# 64CharTestDisp.net
KiCad netlist of a schematic drawn in EAGLE
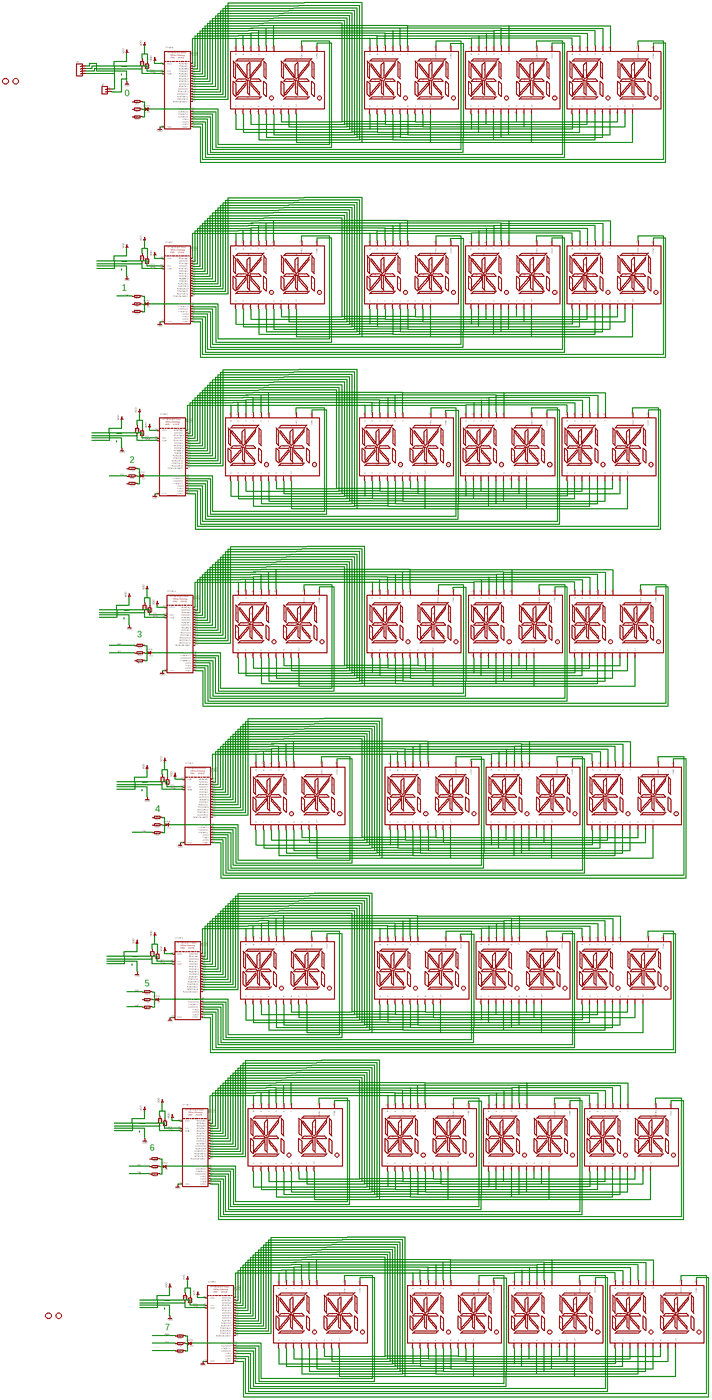
[diagram p0: schematic, sheet 1, overview]
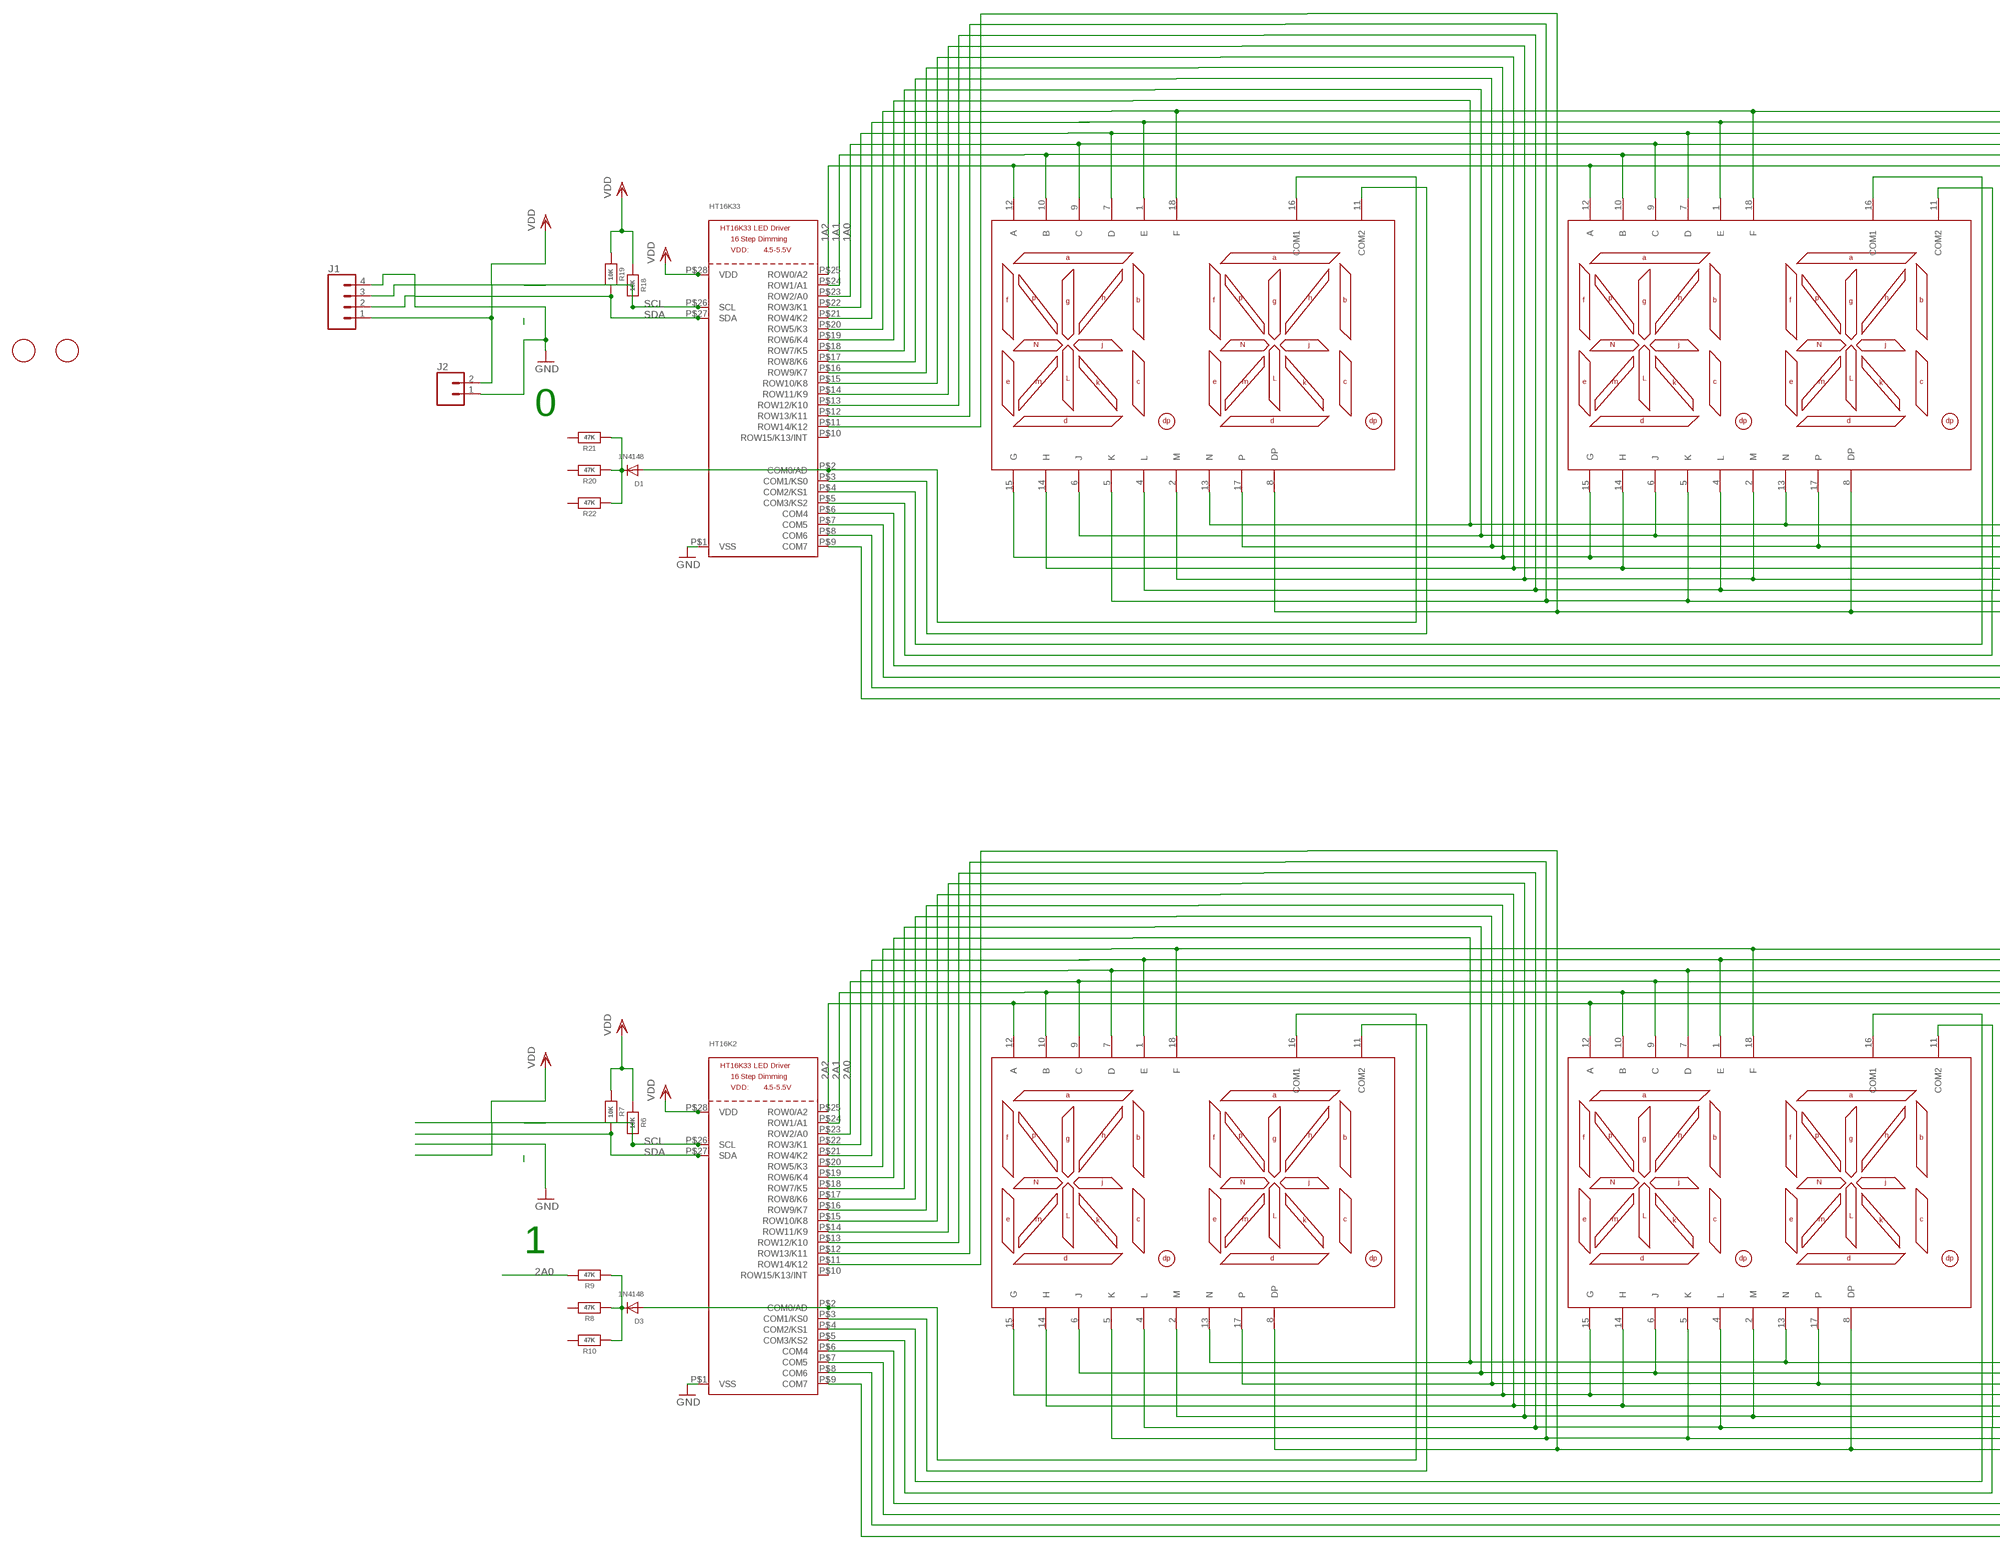
[diagram p1: schematic, sheet 1, part 1 of 8]
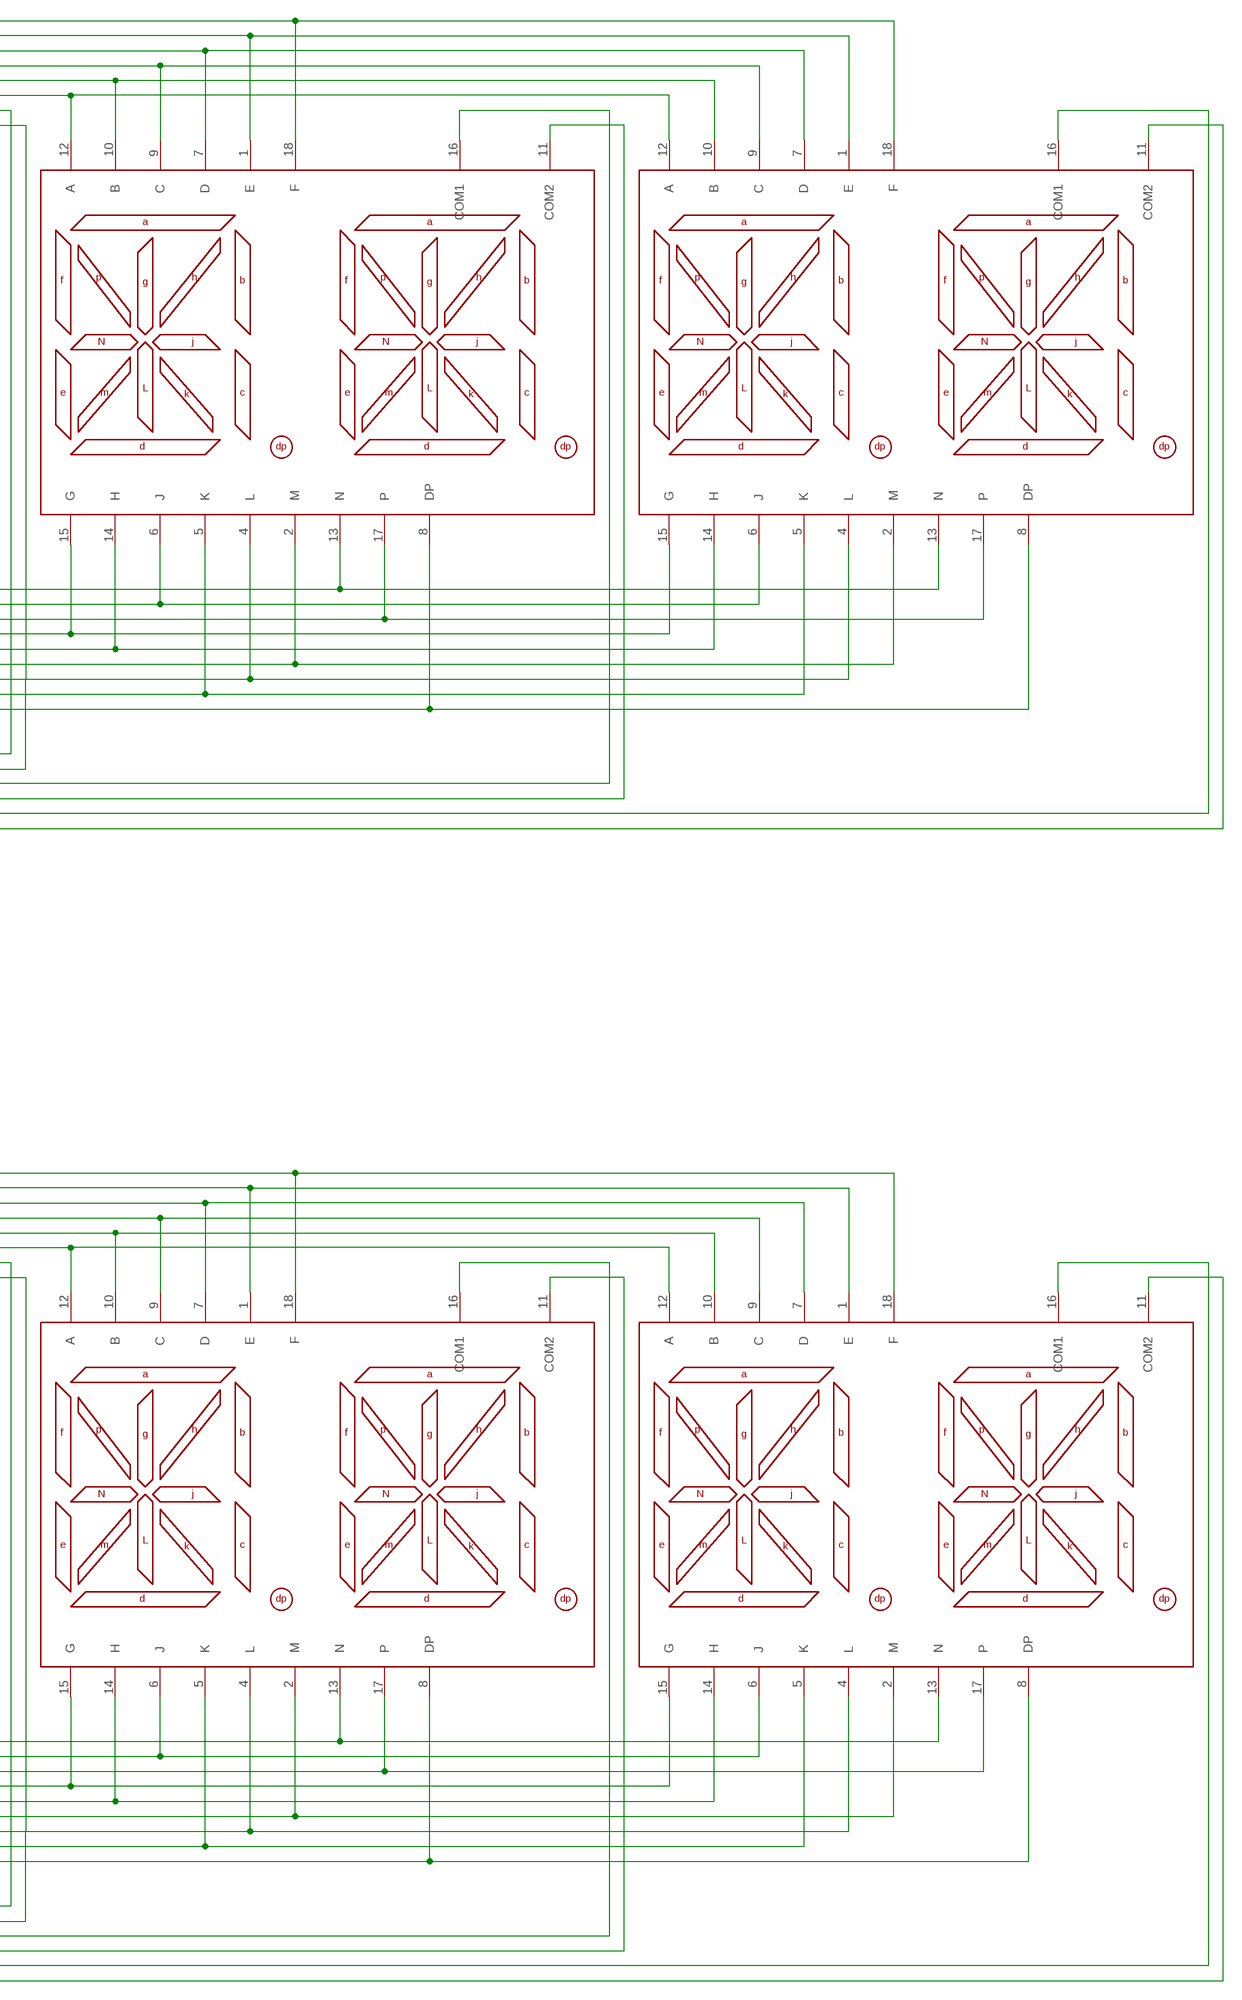
[diagram p2: schematic, sheet 1, part 2 of 8]
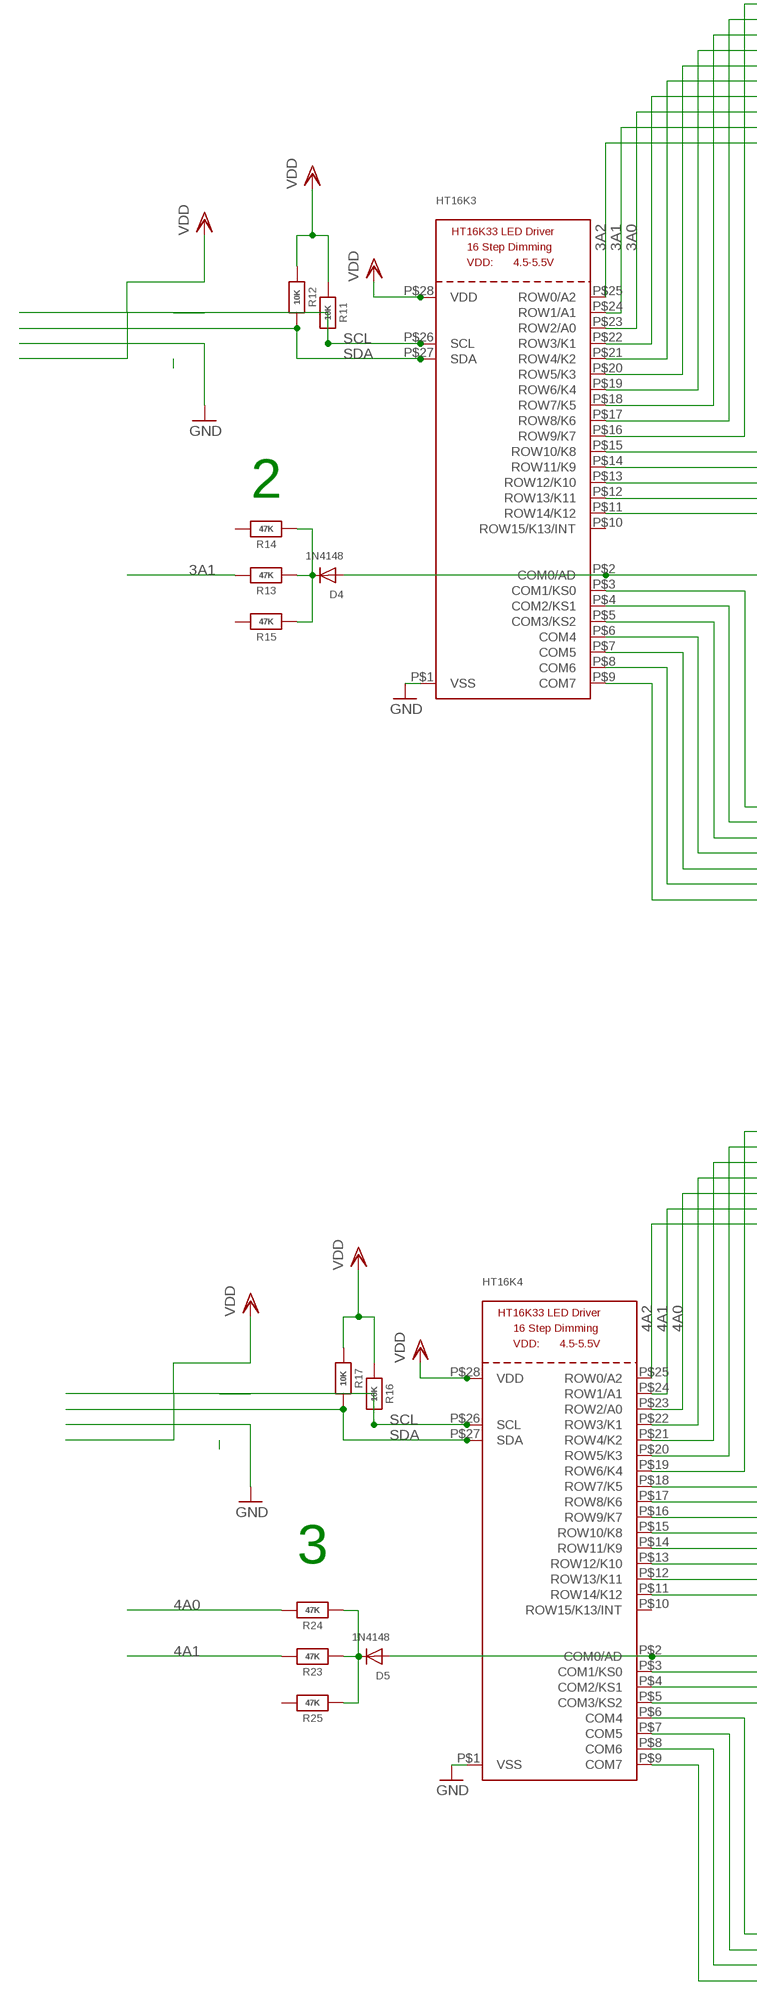
[diagram p3: schematic, sheet 1, part 3 of 8]
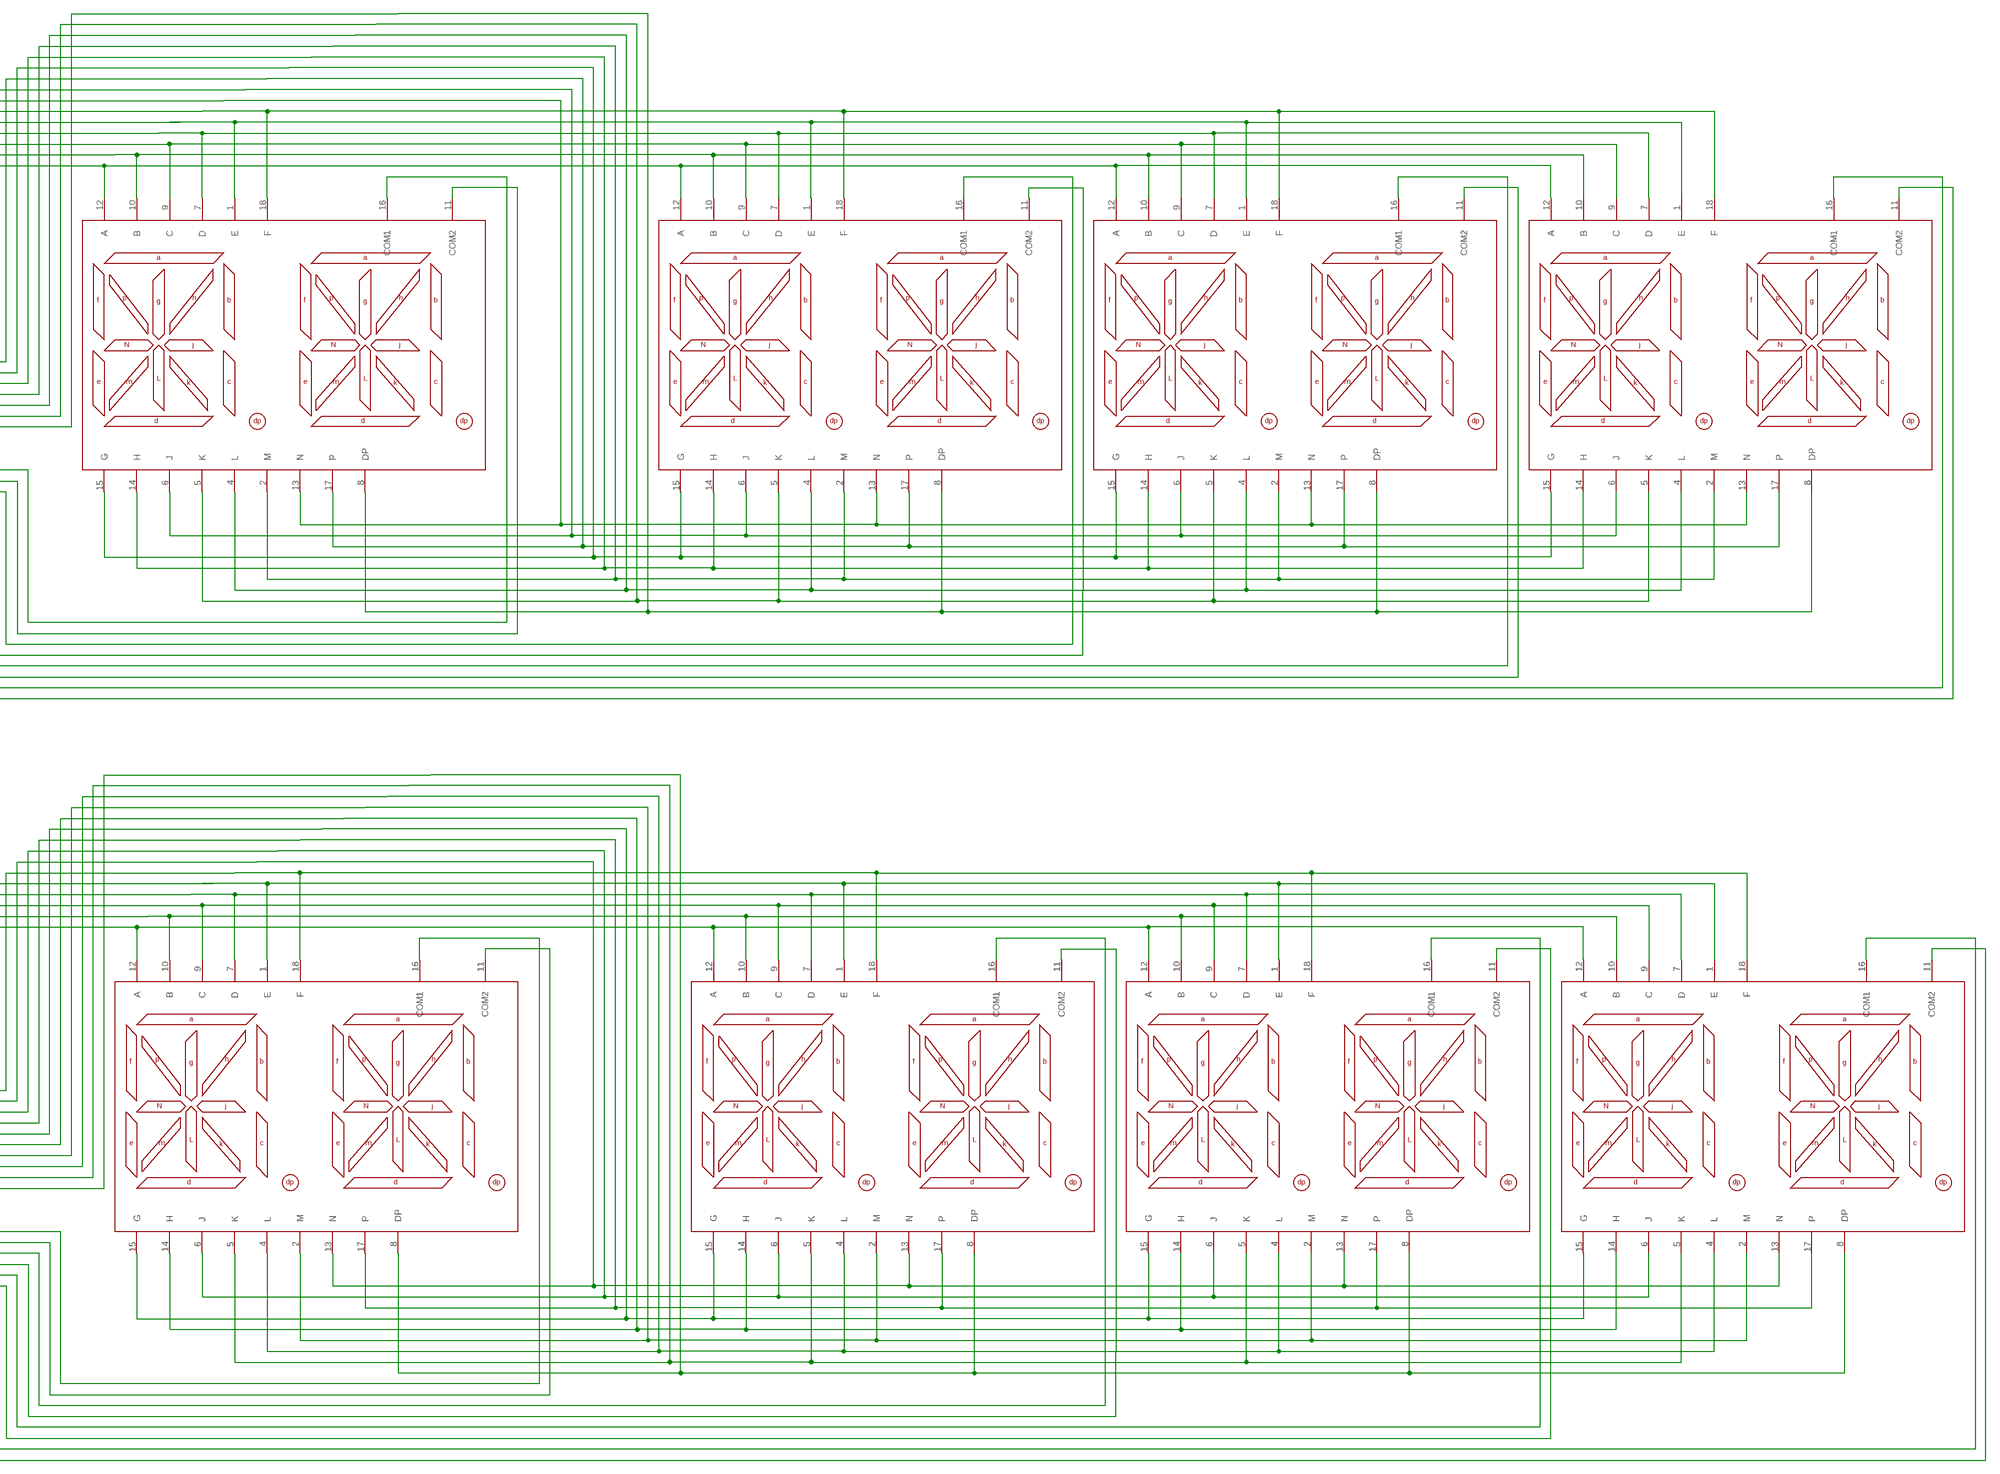
[diagram p4: schematic, sheet 1, part 4 of 8]
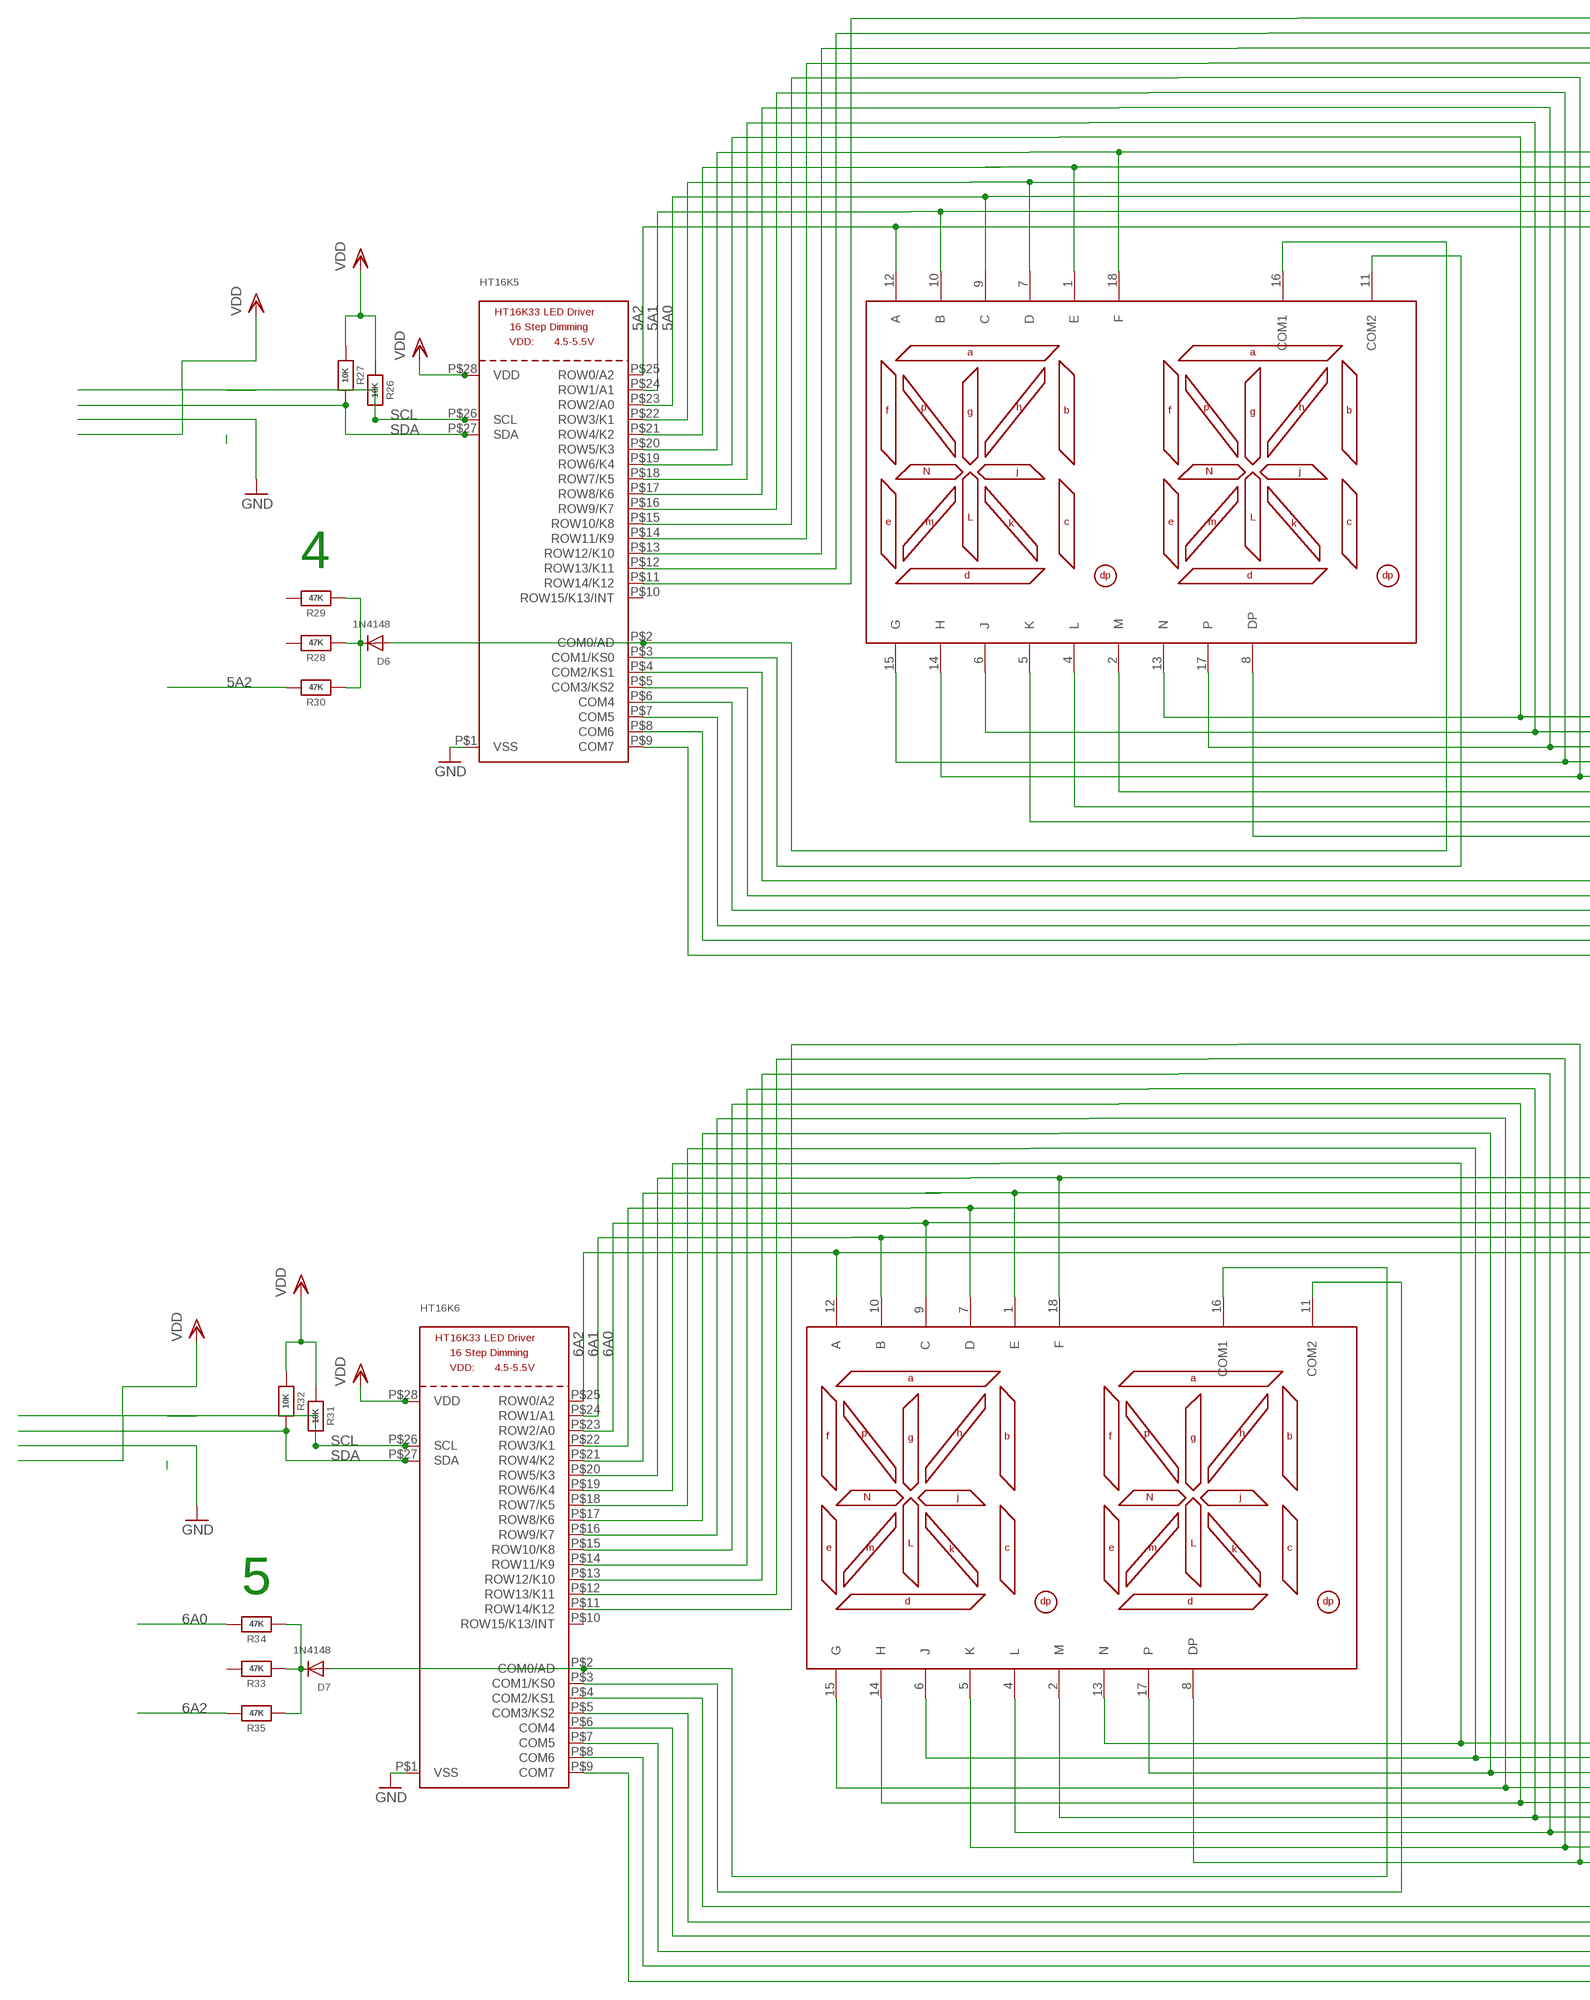
[diagram p5: schematic, sheet 1, part 5 of 8]
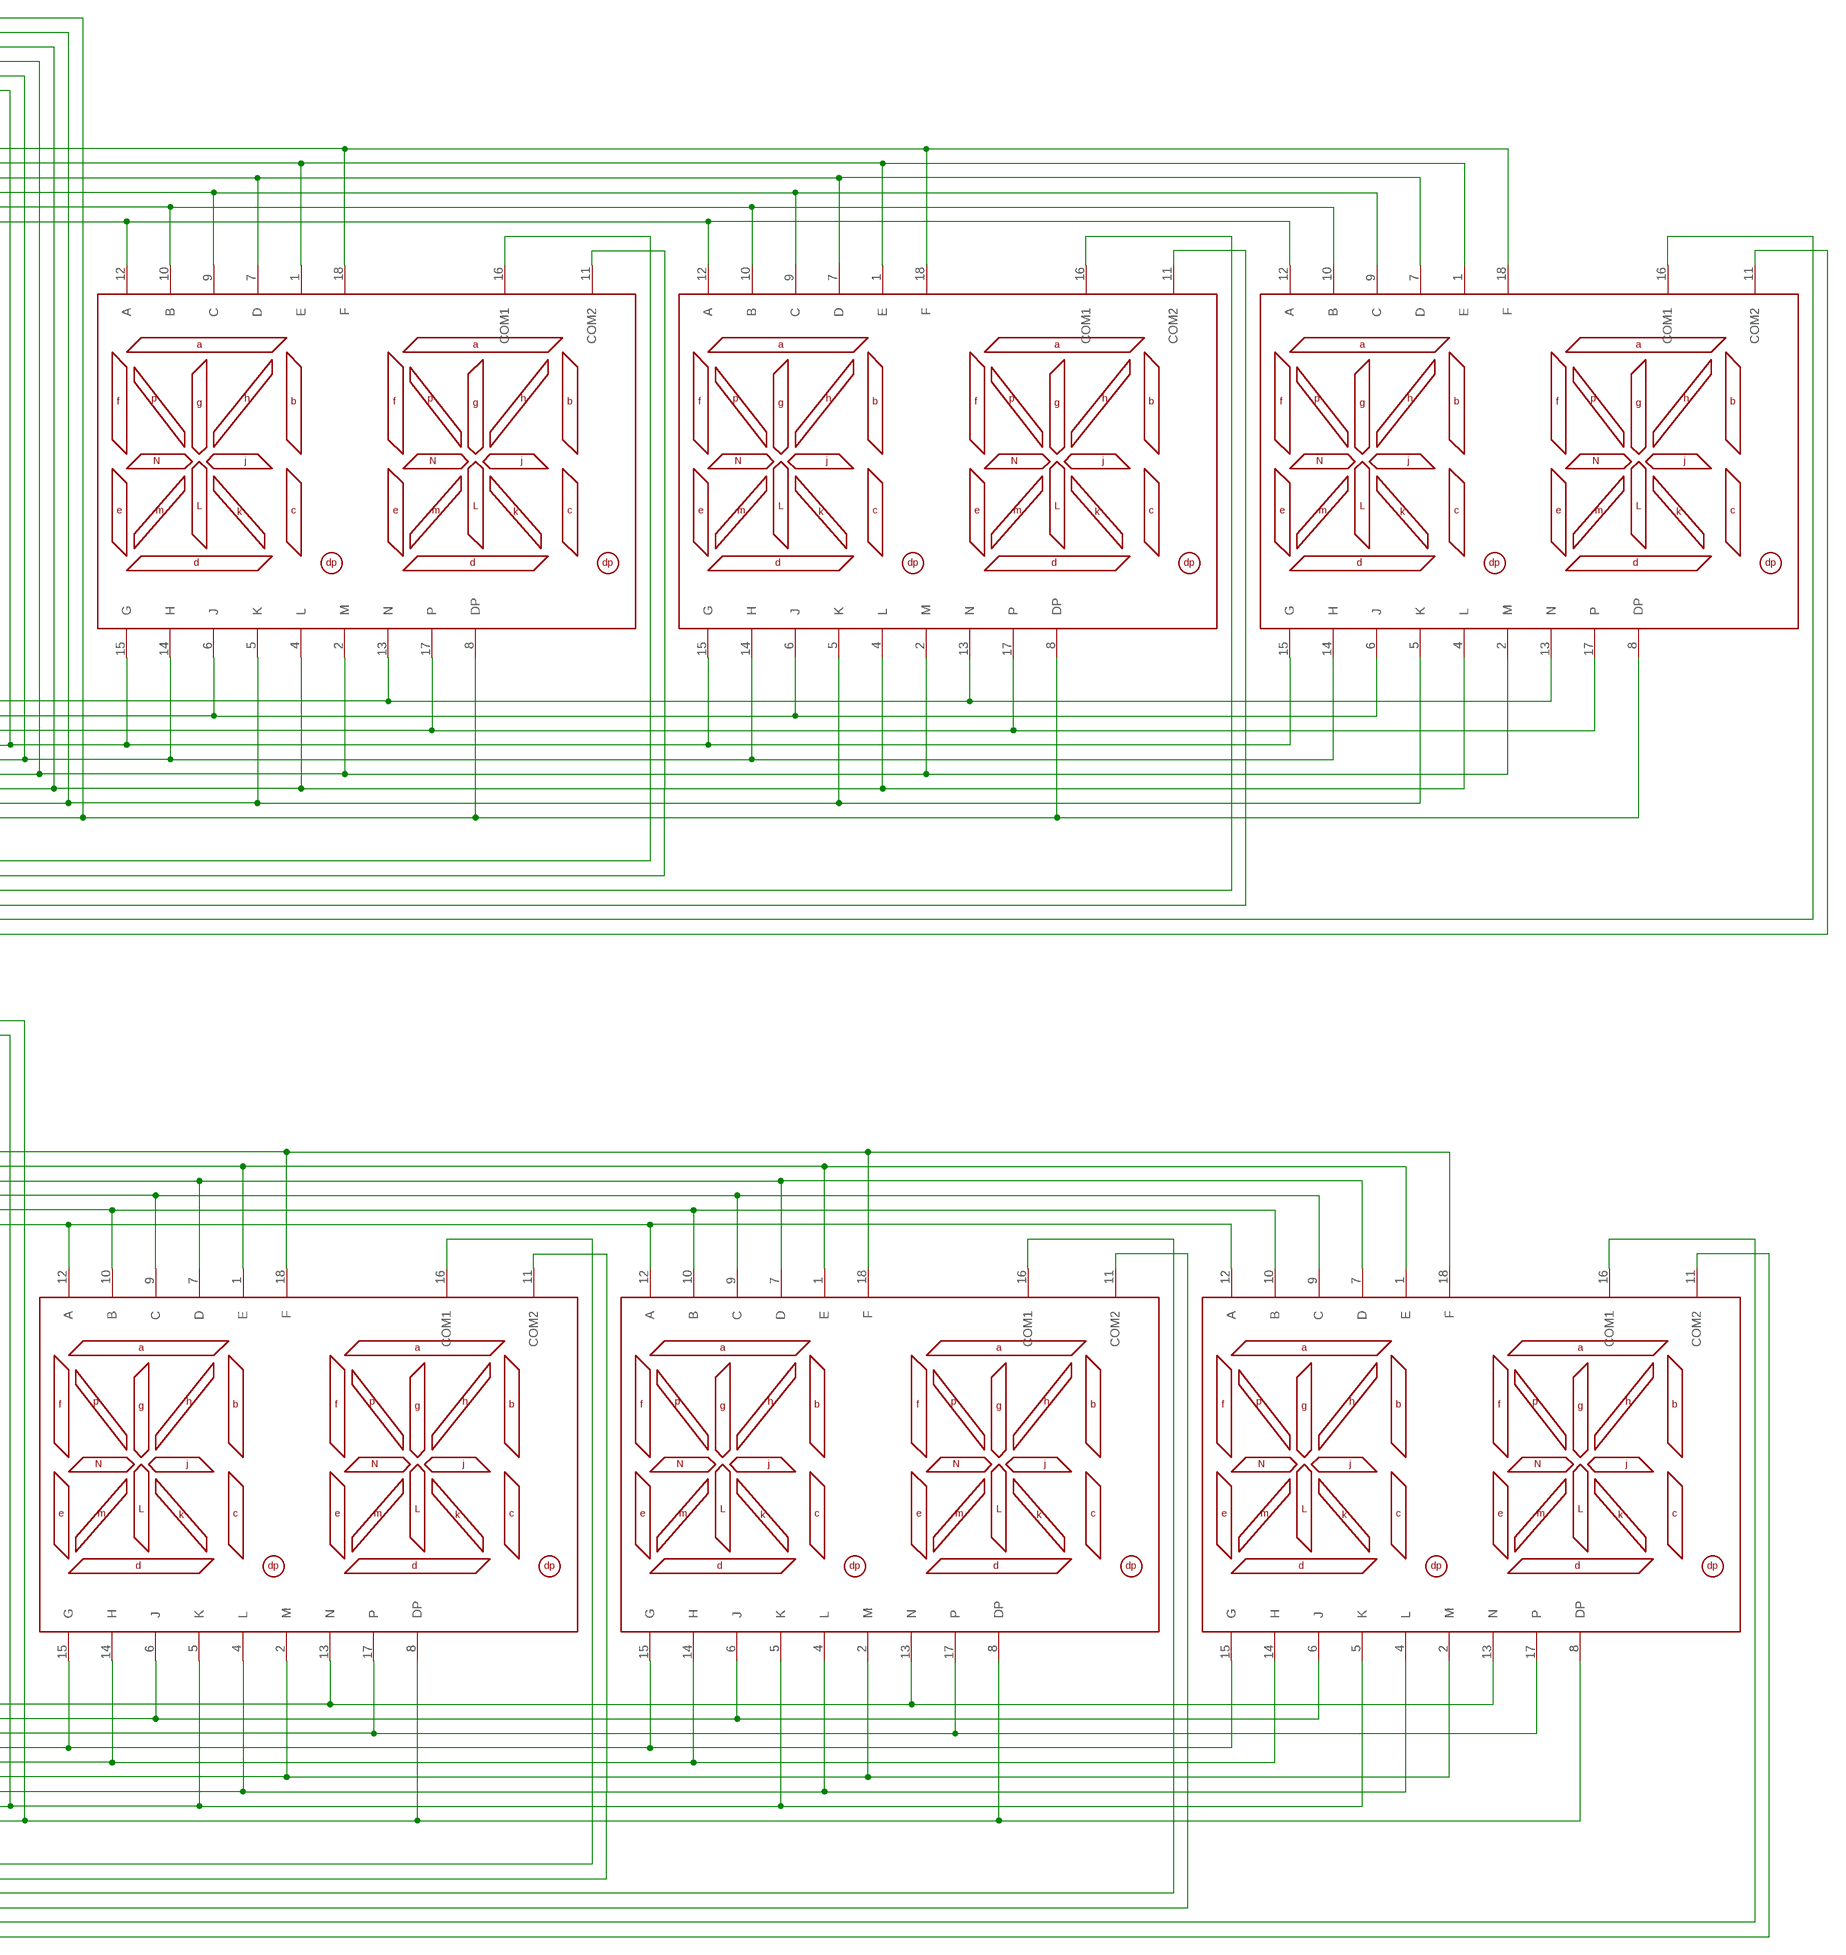
[diagram p6: schematic, sheet 1, part 6 of 8]
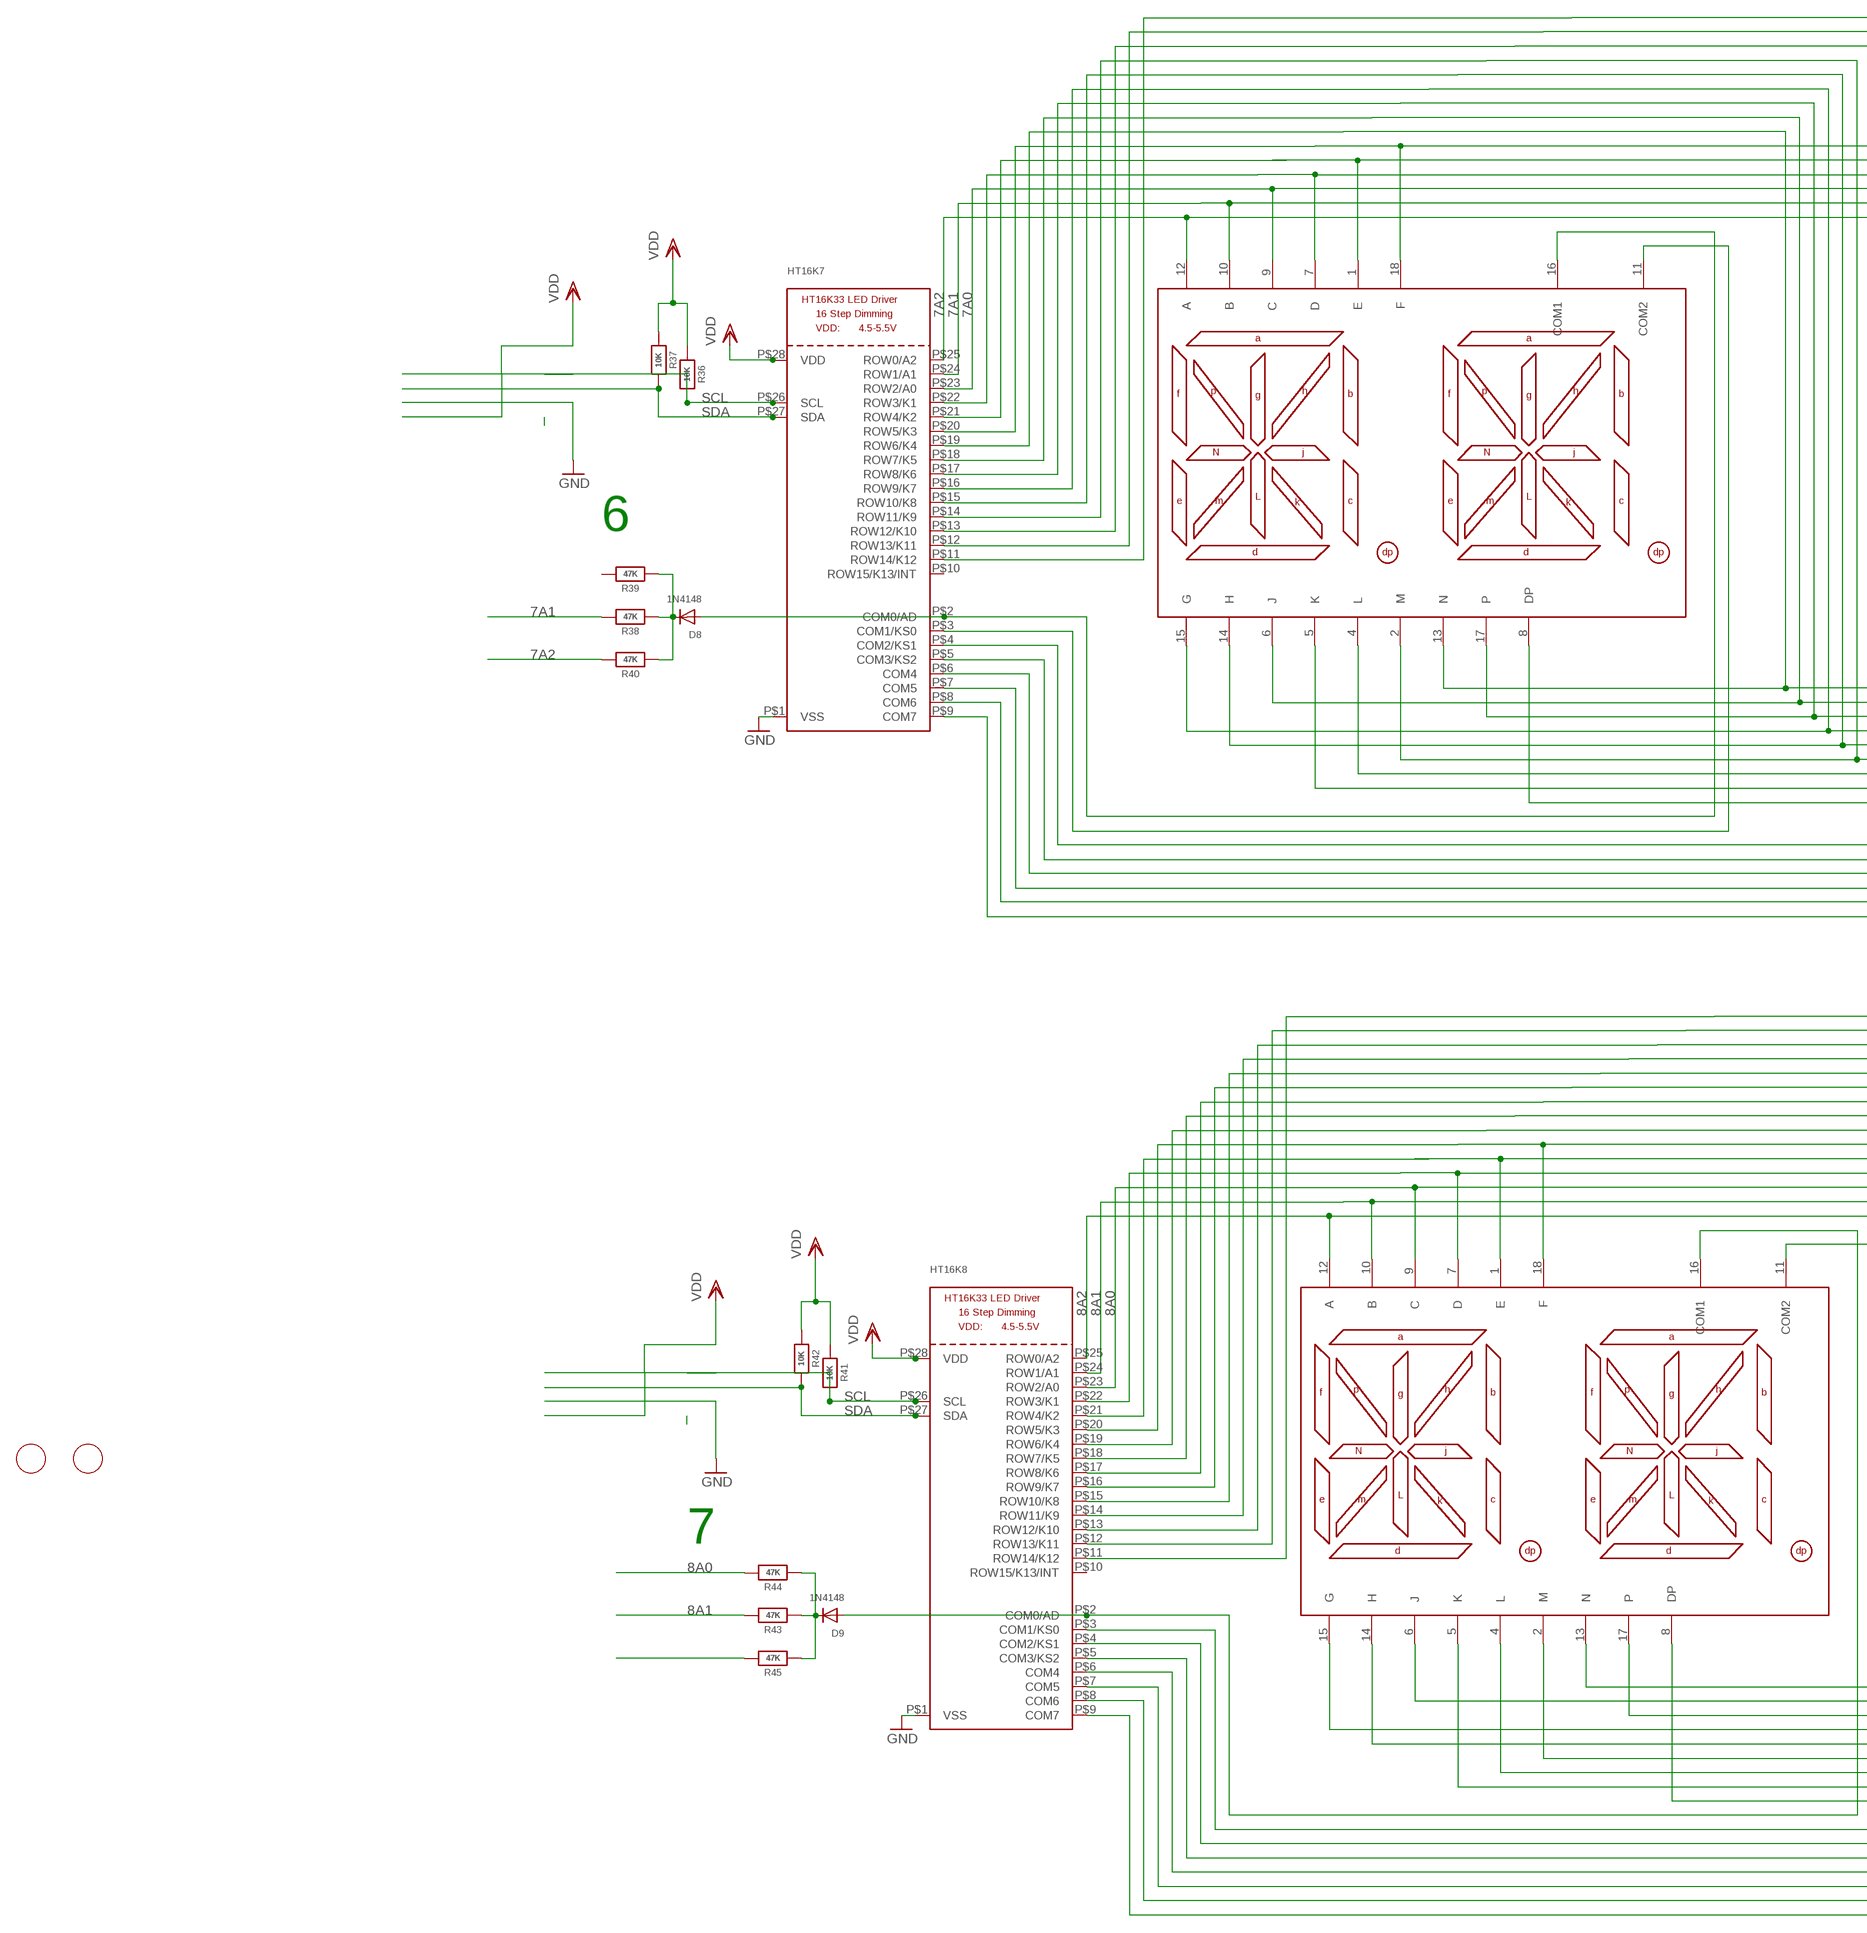
[diagram p7: schematic, sheet 1, part 7 of 8]
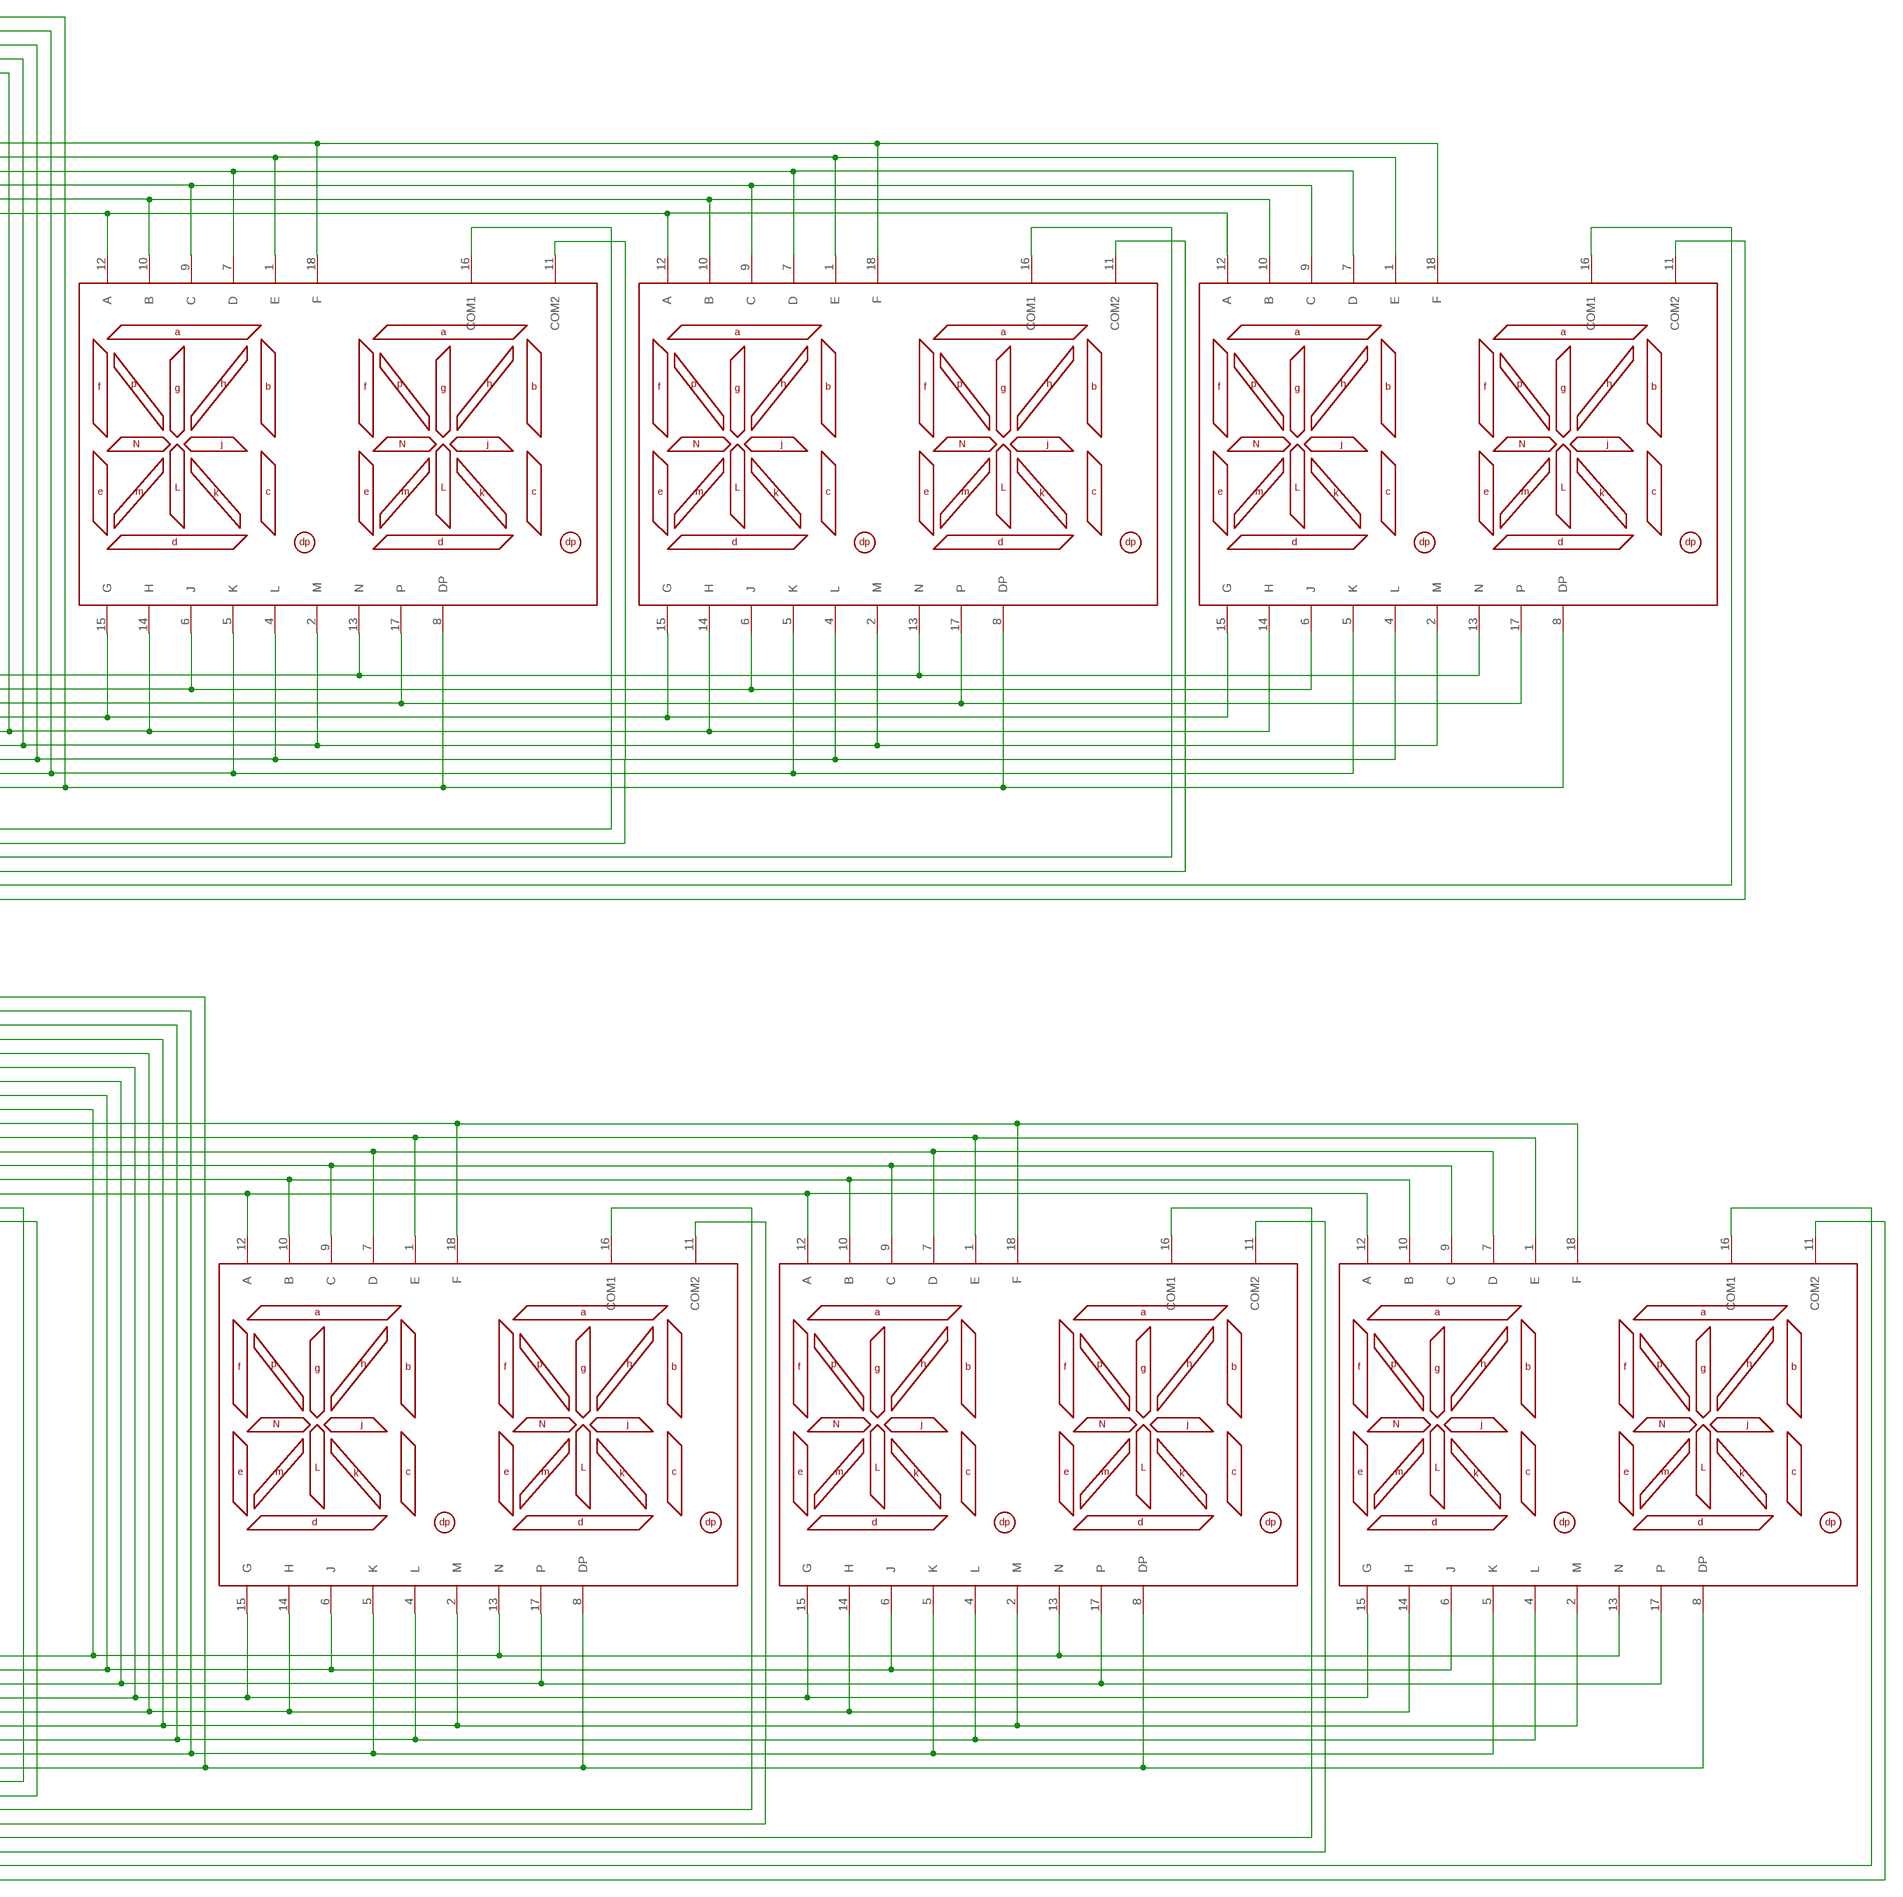
[diagram p8: schematic, sheet 1, part 8 of 8]

(export (version "E")
  (design (tool "Eeschema 10.0.6"))
  (components
    (comp (ref "D1")
      (value "1N4148")
      (footprint "eagle-import:SOD-323F")
      (libsource (lib "eagle-import") (part "DIODESOD-323F"))
    )
    (comp (ref "D3")
      (value "1N4148")
      (footprint "eagle-import:SOD-323F")
      (libsource (lib "eagle-import") (part "DIODESOD-323F"))
    )
    (comp (ref "D4")
      (value "1N4148")
      (footprint "eagle-import:SOD-323F")
      (libsource (lib "eagle-import") (part "DIODESOD-323F"))
    )
    (comp (ref "D5")
      (value "1N4148")
      (footprint "eagle-import:SOD-323F")
      (libsource (lib "eagle-import") (part "DIODESOD-323F"))
    )
    (comp (ref "D6")
      (value "1N4148")
      (footprint "eagle-import:SOD-323F")
      (libsource (lib "eagle-import") (part "DIODESOD-323F"))
    )
    (comp (ref "D7")
      (value "1N4148")
      (footprint "eagle-import:SOD-323F")
      (libsource (lib "eagle-import") (part "DIODESOD-323F"))
    )
    (comp (ref "D8")
      (value "1N4148")
      (footprint "eagle-import:SOD-323F")
      (libsource (lib "eagle-import") (part "DIODESOD-323F"))
    )
    (comp (ref "D9")
      (value "1N4148")
      (footprint "eagle-import:SOD-323F")
      (libsource (lib "eagle-import") (part "DIODESOD-323F"))
    )
    (comp (ref "HT16K2")
      (value "HT16K33_SOP28_SKINNY")
      (footprint "eagle-import:SOP28_300MIL_SKINNY")
      (libsource (lib "eagle-import") (part "HT16K33_SOP28_SKINNY"))
    )
    (comp (ref "HT16K3")
      (value "HT16K33_SOP28_SKINNY")
      (footprint "eagle-import:SOP28_300MIL_SKINNY")
      (libsource (lib "eagle-import") (part "HT16K33_SOP28_SKINNY"))
    )
    (comp (ref "HT16K4")
      (value "HT16K33_SOP28_SKINNY")
      (footprint "eagle-import:SOP28_300MIL_SKINNY")
      (libsource (lib "eagle-import") (part "HT16K33_SOP28_SKINNY"))
    )
    (comp (ref "HT16K5")
      (value "HT16K33_SOP28_SKINNY")
      (footprint "eagle-import:SOP28_300MIL_SKINNY")
      (libsource (lib "eagle-import") (part "HT16K33_SOP28_SKINNY"))
    )
    (comp (ref "HT16K6")
      (value "HT16K33_SOP28_SKINNY")
      (footprint "eagle-import:SOP28_300MIL_SKINNY")
      (libsource (lib "eagle-import") (part "HT16K33_SOP28_SKINNY"))
    )
    (comp (ref "HT16K7")
      (value "HT16K33_SOP28_SKINNY")
      (footprint "eagle-import:SOP28_300MIL_SKINNY")
      (libsource (lib "eagle-import") (part "HT16K33_SOP28_SKINNY"))
    )
    (comp (ref "HT16K8")
      (value "HT16K33_SOP28_SKINNY")
      (footprint "eagle-import:SOP28_300MIL_SKINNY")
      (libsource (lib "eagle-import") (part "HT16K33_SOP28_SKINNY"))
    )
    (comp (ref "HT16K33")
      (value "HT16K33_SOP28_SKINNY")
      (footprint "eagle-import:SOP28_300MIL_SKINNY")
      (libsource (lib "eagle-import") (part "HT16K33_SOP28_SKINNY"))
    )
    (comp (ref "J1")
      (value "CONN_04JST-PTH-VERT")
      (footprint "eagle-import:JST-4-PTH-VERT")
      (libsource (lib "eagle-import") (part "CONN_04JST-PTH-VERT"))
    )
    (comp (ref "J2")
      (value "CONN_023.5MM")
      (footprint "eagle-import:SCREWTERMINAL-3.5MM-2")
      (libsource (lib "eagle-import") (part "CONN_023.5MM"))
    )
    (comp (ref "R6")
      (value "10K")
      (footprint "eagle-import:0805-NO")
      (libsource (lib "eagle-import") (part "RESISTOR0805_NOOUTLINE"))
    )
    (comp (ref "R7")
      (value "10K")
      (footprint "eagle-import:0805-NO")
      (libsource (lib "eagle-import") (part "RESISTOR0805_NOOUTLINE"))
    )
    (comp (ref "R8")
      (value "47K")
      (footprint "eagle-import:0805-NO")
      (libsource (lib "eagle-import") (part "RESISTOR0805_NOOUTLINE"))
    )
    (comp (ref "R9")
      (value "47K")
      (footprint "eagle-import:0805-NO")
      (libsource (lib "eagle-import") (part "RESISTOR0805_NOOUTLINE"))
    )
    (comp (ref "R10")
      (value "47K")
      (footprint "eagle-import:0805-NO")
      (libsource (lib "eagle-import") (part "RESISTOR0805_NOOUTLINE"))
    )
    (comp (ref "R11")
      (value "10K")
      (footprint "eagle-import:0805-NO")
      (libsource (lib "eagle-import") (part "RESISTOR0805_NOOUTLINE"))
    )
    (comp (ref "R12")
      (value "10K")
      (footprint "eagle-import:0805-NO")
      (libsource (lib "eagle-import") (part "RESISTOR0805_NOOUTLINE"))
    )
    (comp (ref "R13")
      (value "47K")
      (footprint "eagle-import:0805-NO")
      (libsource (lib "eagle-import") (part "RESISTOR0805_NOOUTLINE"))
    )
    (comp (ref "R14")
      (value "47K")
      (footprint "eagle-import:0805-NO")
      (libsource (lib "eagle-import") (part "RESISTOR0805_NOOUTLINE"))
    )
    (comp (ref "R15")
      (value "47K")
      (footprint "eagle-import:0805-NO")
      (libsource (lib "eagle-import") (part "RESISTOR0805_NOOUTLINE"))
    )
    (comp (ref "R16")
      (value "10K")
      (footprint "eagle-import:0805-NO")
      (libsource (lib "eagle-import") (part "RESISTOR0805_NOOUTLINE"))
    )
    (comp (ref "R17")
      (value "10K")
      (footprint "eagle-import:0805-NO")
      (libsource (lib "eagle-import") (part "RESISTOR0805_NOOUTLINE"))
    )
    (comp (ref "R18")
      (value "10K")
      (footprint "eagle-import:0805-NO")
      (libsource (lib "eagle-import") (part "RESISTOR0805_NOOUTLINE"))
    )
    (comp (ref "R19")
      (value "10K")
      (footprint "eagle-import:0805-NO")
      (libsource (lib "eagle-import") (part "RESISTOR0805_NOOUTLINE"))
    )
    (comp (ref "R20")
      (value "47K")
      (footprint "eagle-import:0805-NO")
      (libsource (lib "eagle-import") (part "RESISTOR0805_NOOUTLINE"))
    )
    (comp (ref "R21")
      (value "47K")
      (footprint "eagle-import:0805-NO")
      (libsource (lib "eagle-import") (part "RESISTOR0805_NOOUTLINE"))
    )
    (comp (ref "R22")
      (value "47K")
      (footprint "eagle-import:0805-NO")
      (libsource (lib "eagle-import") (part "RESISTOR0805_NOOUTLINE"))
    )
    (comp (ref "R23")
      (value "47K")
      (footprint "eagle-import:0805-NO")
      (libsource (lib "eagle-import") (part "RESISTOR0805_NOOUTLINE"))
    )
    (comp (ref "R24")
      (value "47K")
      (footprint "eagle-import:0805-NO")
      (libsource (lib "eagle-import") (part "RESISTOR0805_NOOUTLINE"))
    )
    (comp (ref "R25")
      (value "47K")
      (footprint "eagle-import:0805-NO")
      (libsource (lib "eagle-import") (part "RESISTOR0805_NOOUTLINE"))
    )
    (comp (ref "R26")
      (value "10K")
      (footprint "eagle-import:0805-NO")
      (libsource (lib "eagle-import") (part "RESISTOR0805_NOOUTLINE"))
    )
    (comp (ref "R27")
      (value "10K")
      (footprint "eagle-import:0805-NO")
      (libsource (lib "eagle-import") (part "RESISTOR0805_NOOUTLINE"))
    )
    (comp (ref "R28")
      (value "47K")
      (footprint "eagle-import:0805-NO")
      (libsource (lib "eagle-import") (part "RESISTOR0805_NOOUTLINE"))
    )
    (comp (ref "R29")
      (value "47K")
      (footprint "eagle-import:0805-NO")
      (libsource (lib "eagle-import") (part "RESISTOR0805_NOOUTLINE"))
    )
    (comp (ref "R30")
      (value "47K")
      (footprint "eagle-import:0805-NO")
      (libsource (lib "eagle-import") (part "RESISTOR0805_NOOUTLINE"))
    )
    (comp (ref "R31")
      (value "10K")
      (footprint "eagle-import:0805-NO")
      (libsource (lib "eagle-import") (part "RESISTOR0805_NOOUTLINE"))
    )
    (comp (ref "R32")
      (value "10K")
      (footprint "eagle-import:0805-NO")
      (libsource (lib "eagle-import") (part "RESISTOR0805_NOOUTLINE"))
    )
    (comp (ref "R33")
      (value "47K")
      (footprint "eagle-import:0805-NO")
      (libsource (lib "eagle-import") (part "RESISTOR0805_NOOUTLINE"))
    )
    (comp (ref "R34")
      (value "47K")
      (footprint "eagle-import:0805-NO")
      (libsource (lib "eagle-import") (part "RESISTOR0805_NOOUTLINE"))
    )
    (comp (ref "R35")
      (value "47K")
      (footprint "eagle-import:0805-NO")
      (libsource (lib "eagle-import") (part "RESISTOR0805_NOOUTLINE"))
    )
    (comp (ref "R36")
      (value "10K")
      (footprint "eagle-import:0805-NO")
      (libsource (lib "eagle-import") (part "RESISTOR0805_NOOUTLINE"))
    )
    (comp (ref "R37")
      (value "10K")
      (footprint "eagle-import:0805-NO")
      (libsource (lib "eagle-import") (part "RESISTOR0805_NOOUTLINE"))
    )
    (comp (ref "R38")
      (value "47K")
      (footprint "eagle-import:0805-NO")
      (libsource (lib "eagle-import") (part "RESISTOR0805_NOOUTLINE"))
    )
    (comp (ref "R39")
      (value "47K")
      (footprint "eagle-import:0805-NO")
      (libsource (lib "eagle-import") (part "RESISTOR0805_NOOUTLINE"))
    )
    (comp (ref "R40")
      (value "47K")
      (footprint "eagle-import:0805-NO")
      (libsource (lib "eagle-import") (part "RESISTOR0805_NOOUTLINE"))
    )
    (comp (ref "R41")
      (value "10K")
      (footprint "eagle-import:0805-NO")
      (libsource (lib "eagle-import") (part "RESISTOR0805_NOOUTLINE"))
    )
    (comp (ref "R42")
      (value "10K")
      (footprint "eagle-import:0805-NO")
      (libsource (lib "eagle-import") (part "RESISTOR0805_NOOUTLINE"))
    )
    (comp (ref "R43")
      (value "47K")
      (footprint "eagle-import:0805-NO")
      (libsource (lib "eagle-import") (part "RESISTOR0805_NOOUTLINE"))
    )
    (comp (ref "R44")
      (value "47K")
      (footprint "eagle-import:0805-NO")
      (libsource (lib "eagle-import") (part "RESISTOR0805_NOOUTLINE"))
    )
    (comp (ref "R45")
      (value "47K")
      (footprint "eagle-import:0805-NO")
      (libsource (lib "eagle-import") (part "RESISTOR0805_NOOUTLINE"))
    )
    (comp (ref "U$2")
      (value "BIG14SEG")
      (footprint "eagle-import:HDSP")
      (libsource (lib "eagle-import") (part "BIG14SEG"))
    )
    (comp (ref "U$3")
      (value "BIG14SEG")
      (footprint "eagle-import:HDSP")
      (libsource (lib "eagle-import") (part "BIG14SEG"))
    )
    (comp (ref "U$4")
      (value "BIG14SEG")
      (footprint "eagle-import:HDSP")
      (libsource (lib "eagle-import") (part "BIG14SEG"))
    )
    (comp (ref "U$5")
      (value "BIG14SEG")
      (footprint "eagle-import:HDSP")
      (libsource (lib "eagle-import") (part "BIG14SEG"))
    )
    (comp (ref "U$11")
      (value "BIG14SEG")
      (footprint "eagle-import:HDSP")
      (libsource (lib "eagle-import") (part "BIG14SEG"))
    )
    (comp (ref "U$12")
      (value "BIG14SEG")
      (footprint "eagle-import:HDSP")
      (libsource (lib "eagle-import") (part "BIG14SEG"))
    )
    (comp (ref "U$13")
      (value "BIG14SEG")
      (footprint "eagle-import:HDSP")
      (libsource (lib "eagle-import") (part "BIG14SEG"))
    )
    (comp (ref "U$14")
      (value "BIG14SEG")
      (footprint "eagle-import:HDSP")
      (libsource (lib "eagle-import") (part "BIG14SEG"))
    )
    (comp (ref "U$15")
      (value "BIG14SEG")
      (footprint "eagle-import:HDSP")
      (libsource (lib "eagle-import") (part "BIG14SEG"))
    )
    (comp (ref "U$16")
      (value "BIG14SEG")
      (footprint "eagle-import:HDSP")
      (libsource (lib "eagle-import") (part "BIG14SEG"))
    )
    (comp (ref "U$17")
      (value "BIG14SEG")
      (footprint "eagle-import:HDSP")
      (libsource (lib "eagle-import") (part "BIG14SEG"))
    )
    (comp (ref "U$18")
      (value "BIG14SEG")
      (footprint "eagle-import:HDSP")
      (libsource (lib "eagle-import") (part "BIG14SEG"))
    )
    (comp (ref "U$19")
      (value "BIG14SEG")
      (footprint "eagle-import:HDSP")
      (libsource (lib "eagle-import") (part "BIG14SEG"))
    )
    (comp (ref "U$20")
      (value "BIG14SEG")
      (footprint "eagle-import:HDSP")
      (libsource (lib "eagle-import") (part "BIG14SEG"))
    )
    (comp (ref "U$21")
      (value "BIG14SEG")
      (footprint "eagle-import:HDSP")
      (libsource (lib "eagle-import") (part "BIG14SEG"))
    )
    (comp (ref "U$22")
      (value "BIG14SEG")
      (footprint "eagle-import:HDSP")
      (libsource (lib "eagle-import") (part "BIG14SEG"))
    )
    (comp (ref "U$23")
      (value "BIG14SEG")
      (footprint "eagle-import:HDSP")
      (libsource (lib "eagle-import") (part "BIG14SEG"))
    )
    (comp (ref "U$24")
      (value "BIG14SEG")
      (footprint "eagle-import:HDSP")
      (libsource (lib "eagle-import") (part "BIG14SEG"))
    )
    (comp (ref "U$25")
      (value "BIG14SEG")
      (footprint "eagle-import:HDSP")
      (libsource (lib "eagle-import") (part "BIG14SEG"))
    )
    (comp (ref "U$26")
      (value "BIG14SEG")
      (footprint "eagle-import:HDSP")
      (libsource (lib "eagle-import") (part "BIG14SEG"))
    )
    (comp (ref "U$27")
      (value "BIG14SEG")
      (footprint "eagle-import:HDSP")
      (libsource (lib "eagle-import") (part "BIG14SEG"))
    )
    (comp (ref "U$28")
      (value "BIG14SEG")
      (footprint "eagle-import:HDSP")
      (libsource (lib "eagle-import") (part "BIG14SEG"))
    )
    (comp (ref "U$29")
      (value "BIG14SEG")
      (footprint "eagle-import:HDSP")
      (libsource (lib "eagle-import") (part "BIG14SEG"))
    )
    (comp (ref "U$30")
      (value "BIG14SEG")
      (footprint "eagle-import:HDSP")
      (libsource (lib "eagle-import") (part "BIG14SEG"))
    )
    (comp (ref "U$31")
      (value "BIG14SEG")
      (footprint "eagle-import:HDSP")
      (libsource (lib "eagle-import") (part "BIG14SEG"))
    )
    (comp (ref "U$32")
      (value "BIG14SEG")
      (footprint "eagle-import:HDSP")
      (libsource (lib "eagle-import") (part "BIG14SEG"))
    )
    (comp (ref "U$33")
      (value "BIG14SEG")
      (footprint "eagle-import:HDSP")
      (libsource (lib "eagle-import") (part "BIG14SEG"))
    )
    (comp (ref "U$34")
      (value "BIG14SEG")
      (footprint "eagle-import:HDSP")
      (libsource (lib "eagle-import") (part "BIG14SEG"))
    )
    (comp (ref "U$35")
      (value "KEYSTONESTANDOFF")
      (footprint "eagle-import:KEYSTONESTANDOFF")
      (libsource (lib "eagle-import") (part "KEYSTONESTANDOFF"))
    )
    (comp (ref "U$36")
      (value "KEYSTONESTANDOFF")
      (footprint "eagle-import:KEYSTONESTANDOFF")
      (libsource (lib "eagle-import") (part "KEYSTONESTANDOFF"))
    )
    (comp (ref "U$37")
      (value "BIG14SEG")
      (footprint "eagle-import:HDSP")
      (libsource (lib "eagle-import") (part "BIG14SEG"))
    )
    (comp (ref "U$38")
      (value "BIG14SEG")
      (footprint "eagle-import:HDSP")
      (libsource (lib "eagle-import") (part "BIG14SEG"))
    )
    (comp (ref "U$39")
      (value "BIG14SEG")
      (footprint "eagle-import:HDSP")
      (libsource (lib "eagle-import") (part "BIG14SEG"))
    )
    (comp (ref "U$40")
      (value "BIG14SEG")
      (footprint "eagle-import:HDSP")
      (libsource (lib "eagle-import") (part "BIG14SEG"))
    )
    (comp (ref "U$41")
      (value "KEYSTONESTANDOFF")
      (footprint "eagle-import:KEYSTONESTANDOFF")
      (libsource (lib "eagle-import") (part "KEYSTONESTANDOFF"))
    )
    (comp (ref "U$42")
      (value "KEYSTONESTANDOFF")
      (footprint "eagle-import:KEYSTONESTANDOFF")
      (libsource (lib "eagle-import") (part "KEYSTONESTANDOFF"))
    )
  )
  (nets
    (net (code "1") (name "/1A0") (class "Default")
      (node (ref "HT16K33") (pin "P$23") (pinfunction "ROW2/A0_P$23") (pintype "bidirectional"))
      (node (ref "U$2") (pin "9") (pinfunction "C_9") (pintype "bidirectional"))
      (node (ref "U$3") (pin "9") (pinfunction "C_9") (pintype "bidirectional"))
      (node (ref "U$4") (pin "9") (pinfunction "C_9") (pintype "bidirectional"))
      (node (ref "U$5") (pin "9") (pinfunction "C_9") (pintype "bidirectional"))
    )
    (net (code "2") (name "/1A1") (class "Default")
      (node (ref "HT16K33") (pin "P$24") (pinfunction "ROW1/A1_P$24") (pintype "bidirectional"))
      (node (ref "U$2") (pin "10") (pinfunction "B_10") (pintype "bidirectional"))
      (node (ref "U$3") (pin "10") (pinfunction "B_10") (pintype "bidirectional"))
      (node (ref "U$4") (pin "10") (pinfunction "B_10") (pintype "bidirectional"))
      (node (ref "U$5") (pin "10") (pinfunction "B_10") (pintype "bidirectional"))
    )
    (net (code "3") (name "/1A2") (class "Default")
      (node (ref "HT16K33") (pin "P$25") (pinfunction "ROW0/A2_P$25") (pintype "bidirectional"))
      (node (ref "U$2") (pin "12") (pinfunction "A_12") (pintype "bidirectional"))
      (node (ref "U$3") (pin "12") (pinfunction "A_12") (pintype "bidirectional"))
      (node (ref "U$4") (pin "12") (pinfunction "A_12") (pintype "bidirectional"))
      (node (ref "U$5") (pin "12") (pinfunction "A_12") (pintype "bidirectional"))
    )
    (net (code "4") (name "/2A0") (class "Default")
      (node (ref "HT16K2") (pin "P$23") (pinfunction "ROW2/A0_P$23") (pintype "bidirectional"))
      (node (ref "R9") (pin "2") (pinfunction "2_2") (pintype "passive"))
      (node (ref "U$11") (pin "9") (pinfunction "C_9") (pintype "bidirectional"))
      (node (ref "U$12") (pin "9") (pinfunction "C_9") (pintype "bidirectional"))
      (node (ref "U$13") (pin "9") (pinfunction "C_9") (pintype "bidirectional"))
      (node (ref "U$14") (pin "9") (pinfunction "C_9") (pintype "bidirectional"))
    )
    (net (code "5") (name "/2A1") (class "Default")
      (node (ref "HT16K2") (pin "P$24") (pinfunction "ROW1/A1_P$24") (pintype "bidirectional"))
      (node (ref "U$11") (pin "10") (pinfunction "B_10") (pintype "bidirectional"))
      (node (ref "U$12") (pin "10") (pinfunction "B_10") (pintype "bidirectional"))
      (node (ref "U$13") (pin "10") (pinfunction "B_10") (pintype "bidirectional"))
      (node (ref "U$14") (pin "10") (pinfunction "B_10") (pintype "bidirectional"))
    )
    (net (code "6") (name "/2A2") (class "Default")
      (node (ref "HT16K2") (pin "P$25") (pinfunction "ROW0/A2_P$25") (pintype "bidirectional"))
      (node (ref "U$11") (pin "12") (pinfunction "A_12") (pintype "bidirectional"))
      (node (ref "U$12") (pin "12") (pinfunction "A_12") (pintype "bidirectional"))
      (node (ref "U$13") (pin "12") (pinfunction "A_12") (pintype "bidirectional"))
      (node (ref "U$14") (pin "12") (pinfunction "A_12") (pintype "bidirectional"))
    )
    (net (code "7") (name "/3A0") (class "Default")
      (node (ref "HT16K3") (pin "P$23") (pinfunction "ROW2/A0_P$23") (pintype "bidirectional"))
      (node (ref "U$15") (pin "9") (pinfunction "C_9") (pintype "bidirectional"))
      (node (ref "U$16") (pin "9") (pinfunction "C_9") (pintype "bidirectional"))
      (node (ref "U$17") (pin "9") (pinfunction "C_9") (pintype "bidirectional"))
      (node (ref "U$18") (pin "9") (pinfunction "C_9") (pintype "bidirectional"))
    )
    (net (code "8") (name "/3A1") (class "Default")
      (node (ref "HT16K3") (pin "P$24") (pinfunction "ROW1/A1_P$24") (pintype "bidirectional"))
      (node (ref "R13") (pin "2") (pinfunction "2_2") (pintype "passive"))
      (node (ref "U$15") (pin "10") (pinfunction "B_10") (pintype "bidirectional"))
      (node (ref "U$16") (pin "10") (pinfunction "B_10") (pintype "bidirectional"))
      (node (ref "U$17") (pin "10") (pinfunction "B_10") (pintype "bidirectional"))
      (node (ref "U$18") (pin "10") (pinfunction "B_10") (pintype "bidirectional"))
    )
    (net (code "9") (name "/3A2") (class "Default")
      (node (ref "HT16K3") (pin "P$25") (pinfunction "ROW0/A2_P$25") (pintype "bidirectional"))
      (node (ref "U$15") (pin "12") (pinfunction "A_12") (pintype "bidirectional"))
      (node (ref "U$16") (pin "12") (pinfunction "A_12") (pintype "bidirectional"))
      (node (ref "U$17") (pin "12") (pinfunction "A_12") (pintype "bidirectional"))
      (node (ref "U$18") (pin "12") (pinfunction "A_12") (pintype "bidirectional"))
    )
    (net (code "10") (name "/4A0") (class "Default")
      (node (ref "HT16K4") (pin "P$23") (pinfunction "ROW2/A0_P$23") (pintype "bidirectional"))
      (node (ref "R24") (pin "2") (pinfunction "2_2") (pintype "passive"))
      (node (ref "U$19") (pin "9") (pinfunction "C_9") (pintype "bidirectional"))
      (node (ref "U$20") (pin "9") (pinfunction "C_9") (pintype "bidirectional"))
      (node (ref "U$21") (pin "9") (pinfunction "C_9") (pintype "bidirectional"))
      (node (ref "U$22") (pin "9") (pinfunction "C_9") (pintype "bidirectional"))
    )
    (net (code "11") (name "/4A1") (class "Default")
      (node (ref "HT16K4") (pin "P$24") (pinfunction "ROW1/A1_P$24") (pintype "bidirectional"))
      (node (ref "R23") (pin "2") (pinfunction "2_2") (pintype "passive"))
      (node (ref "U$19") (pin "10") (pinfunction "B_10") (pintype "bidirectional"))
      (node (ref "U$20") (pin "10") (pinfunction "B_10") (pintype "bidirectional"))
      (node (ref "U$21") (pin "10") (pinfunction "B_10") (pintype "bidirectional"))
      (node (ref "U$22") (pin "10") (pinfunction "B_10") (pintype "bidirectional"))
    )
    (net (code "12") (name "/4A2") (class "Default")
      (node (ref "HT16K4") (pin "P$25") (pinfunction "ROW0/A2_P$25") (pintype "bidirectional"))
      (node (ref "U$19") (pin "12") (pinfunction "A_12") (pintype "bidirectional"))
      (node (ref "U$20") (pin "12") (pinfunction "A_12") (pintype "bidirectional"))
      (node (ref "U$21") (pin "12") (pinfunction "A_12") (pintype "bidirectional"))
      (node (ref "U$22") (pin "12") (pinfunction "A_12") (pintype "bidirectional"))
    )
    (net (code "13") (name "/5A0") (class "Default")
      (node (ref "HT16K5") (pin "P$23") (pinfunction "ROW2/A0_P$23") (pintype "bidirectional"))
      (node (ref "U$23") (pin "9") (pinfunction "C_9") (pintype "bidirectional"))
      (node (ref "U$24") (pin "9") (pinfunction "C_9") (pintype "bidirectional"))
      (node (ref "U$25") (pin "9") (pinfunction "C_9") (pintype "bidirectional"))
      (node (ref "U$26") (pin "9") (pinfunction "C_9") (pintype "bidirectional"))
    )
    (net (code "14") (name "/5A1") (class "Default")
      (node (ref "HT16K5") (pin "P$24") (pinfunction "ROW1/A1_P$24") (pintype "bidirectional"))
      (node (ref "U$23") (pin "10") (pinfunction "B_10") (pintype "bidirectional"))
      (node (ref "U$24") (pin "10") (pinfunction "B_10") (pintype "bidirectional"))
      (node (ref "U$25") (pin "10") (pinfunction "B_10") (pintype "bidirectional"))
      (node (ref "U$26") (pin "10") (pinfunction "B_10") (pintype "bidirectional"))
    )
    (net (code "15") (name "/5A2") (class "Default")
      (node (ref "HT16K5") (pin "P$25") (pinfunction "ROW0/A2_P$25") (pintype "bidirectional"))
      (node (ref "R30") (pin "2") (pinfunction "2_2") (pintype "passive"))
      (node (ref "U$23") (pin "12") (pinfunction "A_12") (pintype "bidirectional"))
      (node (ref "U$24") (pin "12") (pinfunction "A_12") (pintype "bidirectional"))
      (node (ref "U$25") (pin "12") (pinfunction "A_12") (pintype "bidirectional"))
      (node (ref "U$26") (pin "12") (pinfunction "A_12") (pintype "bidirectional"))
    )
    (net (code "16") (name "/6A0") (class "Default")
      (node (ref "HT16K6") (pin "P$23") (pinfunction "ROW2/A0_P$23") (pintype "bidirectional"))
      (node (ref "R34") (pin "2") (pinfunction "2_2") (pintype "passive"))
      (node (ref "U$27") (pin "9") (pinfunction "C_9") (pintype "bidirectional"))
      (node (ref "U$28") (pin "9") (pinfunction "C_9") (pintype "bidirectional"))
      (node (ref "U$29") (pin "9") (pinfunction "C_9") (pintype "bidirectional"))
      (node (ref "U$30") (pin "9") (pinfunction "C_9") (pintype "bidirectional"))
    )
    (net (code "17") (name "/6A1") (class "Default")
      (node (ref "HT16K6") (pin "P$24") (pinfunction "ROW1/A1_P$24") (pintype "bidirectional"))
      (node (ref "U$27") (pin "10") (pinfunction "B_10") (pintype "bidirectional"))
      (node (ref "U$28") (pin "10") (pinfunction "B_10") (pintype "bidirectional"))
      (node (ref "U$29") (pin "10") (pinfunction "B_10") (pintype "bidirectional"))
      (node (ref "U$30") (pin "10") (pinfunction "B_10") (pintype "bidirectional"))
    )
    (net (code "18") (name "/6A2") (class "Default")
      (node (ref "HT16K6") (pin "P$25") (pinfunction "ROW0/A2_P$25") (pintype "bidirectional"))
      (node (ref "R35") (pin "2") (pinfunction "2_2") (pintype "passive"))
      (node (ref "U$27") (pin "12") (pinfunction "A_12") (pintype "bidirectional"))
      (node (ref "U$28") (pin "12") (pinfunction "A_12") (pintype "bidirectional"))
      (node (ref "U$29") (pin "12") (pinfunction "A_12") (pintype "bidirectional"))
      (node (ref "U$30") (pin "12") (pinfunction "A_12") (pintype "bidirectional"))
    )
    (net (code "19") (name "/7A0") (class "Default")
      (node (ref "HT16K7") (pin "P$23") (pinfunction "ROW2/A0_P$23") (pintype "bidirectional"))
      (node (ref "U$31") (pin "9") (pinfunction "C_9") (pintype "bidirectional"))
      (node (ref "U$32") (pin "9") (pinfunction "C_9") (pintype "bidirectional"))
      (node (ref "U$33") (pin "9") (pinfunction "C_9") (pintype "bidirectional"))
      (node (ref "U$34") (pin "9") (pinfunction "C_9") (pintype "bidirectional"))
    )
    (net (code "20") (name "/7A1") (class "Default")
      (node (ref "HT16K7") (pin "P$24") (pinfunction "ROW1/A1_P$24") (pintype "bidirectional"))
      (node (ref "R38") (pin "2") (pinfunction "2_2") (pintype "passive"))
      (node (ref "U$31") (pin "10") (pinfunction "B_10") (pintype "bidirectional"))
      (node (ref "U$32") (pin "10") (pinfunction "B_10") (pintype "bidirectional"))
      (node (ref "U$33") (pin "10") (pinfunction "B_10") (pintype "bidirectional"))
      (node (ref "U$34") (pin "10") (pinfunction "B_10") (pintype "bidirectional"))
    )
    (net (code "21") (name "/7A2") (class "Default")
      (node (ref "HT16K7") (pin "P$25") (pinfunction "ROW0/A2_P$25") (pintype "bidirectional"))
      (node (ref "R40") (pin "2") (pinfunction "2_2") (pintype "passive"))
      (node (ref "U$31") (pin "12") (pinfunction "A_12") (pintype "bidirectional"))
      (node (ref "U$32") (pin "12") (pinfunction "A_12") (pintype "bidirectional"))
      (node (ref "U$33") (pin "12") (pinfunction "A_12") (pintype "bidirectional"))
      (node (ref "U$34") (pin "12") (pinfunction "A_12") (pintype "bidirectional"))
    )
    (net (code "22") (name "/8A0") (class "Default")
      (node (ref "HT16K8") (pin "P$23") (pinfunction "ROW2/A0_P$23") (pintype "bidirectional"))
      (node (ref "R44") (pin "2") (pinfunction "2_2") (pintype "passive"))
      (node (ref "U$37") (pin "9") (pinfunction "C_9") (pintype "bidirectional"))
      (node (ref "U$38") (pin "9") (pinfunction "C_9") (pintype "bidirectional"))
      (node (ref "U$39") (pin "9") (pinfunction "C_9") (pintype "bidirectional"))
      (node (ref "U$40") (pin "9") (pinfunction "C_9") (pintype "bidirectional"))
    )
    (net (code "23") (name "/8A1") (class "Default")
      (node (ref "HT16K8") (pin "P$24") (pinfunction "ROW1/A1_P$24") (pintype "bidirectional"))
      (node (ref "R43") (pin "2") (pinfunction "2_2") (pintype "passive"))
      (node (ref "U$37") (pin "10") (pinfunction "B_10") (pintype "bidirectional"))
      (node (ref "U$38") (pin "10") (pinfunction "B_10") (pintype "bidirectional"))
      (node (ref "U$39") (pin "10") (pinfunction "B_10") (pintype "bidirectional"))
      (node (ref "U$40") (pin "10") (pinfunction "B_10") (pintype "bidirectional"))
    )
    (net (code "24") (name "/8A2") (class "Default")
      (node (ref "HT16K8") (pin "P$25") (pinfunction "ROW0/A2_P$25") (pintype "bidirectional"))
      (node (ref "R45") (pin "2") (pinfunction "2_2") (pintype "passive"))
      (node (ref "U$37") (pin "12") (pinfunction "A_12") (pintype "bidirectional"))
      (node (ref "U$38") (pin "12") (pinfunction "A_12") (pintype "bidirectional"))
      (node (ref "U$39") (pin "12") (pinfunction "A_12") (pintype "bidirectional"))
      (node (ref "U$40") (pin "12") (pinfunction "A_12") (pintype "bidirectional"))
    )
    (net (code "25") (name "/SCL") (class "Default")
      (node (ref "HT16K2") (pin "P$26") (pinfunction "SCL_P$26") (pintype "bidirectional"))
      (node (ref "HT16K3") (pin "P$26") (pinfunction "SCL_P$26") (pintype "bidirectional"))
      (node (ref "HT16K33") (pin "P$26") (pinfunction "SCL_P$26") (pintype "bidirectional"))
      (node (ref "HT16K4") (pin "P$26") (pinfunction "SCL_P$26") (pintype "bidirectional"))
      (node (ref "HT16K5") (pin "P$26") (pinfunction "SCL_P$26") (pintype "bidirectional"))
      (node (ref "HT16K6") (pin "P$26") (pinfunction "SCL_P$26") (pintype "bidirectional"))
      (node (ref "HT16K7") (pin "P$26") (pinfunction "SCL_P$26") (pintype "bidirectional"))
      (node (ref "HT16K8") (pin "P$26") (pinfunction "SCL_P$26") (pintype "bidirectional"))
      (node (ref "J1") (pin "3") (pinfunction "3_3") (pintype "passive"))
      (node (ref "R11") (pin "2") (pinfunction "2_2") (pintype "passive"))
      (node (ref "R16") (pin "2") (pinfunction "2_2") (pintype "passive"))
      (node (ref "R18") (pin "2") (pinfunction "2_2") (pintype "passive"))
      (node (ref "R26") (pin "2") (pinfunction "2_2") (pintype "passive"))
      (node (ref "R31") (pin "2") (pinfunction "2_2") (pintype "passive"))
      (node (ref "R36") (pin "2") (pinfunction "2_2") (pintype "passive"))
      (node (ref "R41") (pin "2") (pinfunction "2_2") (pintype "passive"))
      (node (ref "R6") (pin "2") (pinfunction "2_2") (pintype "passive"))
    )
    (net (code "26") (name "/SDA") (class "Default")
      (node (ref "HT16K2") (pin "P$27") (pinfunction "SDA_P$27") (pintype "bidirectional"))
      (node (ref "HT16K3") (pin "P$27") (pinfunction "SDA_P$27") (pintype "bidirectional"))
      (node (ref "HT16K33") (pin "P$27") (pinfunction "SDA_P$27") (pintype "bidirectional"))
      (node (ref "HT16K4") (pin "P$27") (pinfunction "SDA_P$27") (pintype "bidirectional"))
      (node (ref "HT16K5") (pin "P$27") (pinfunction "SDA_P$27") (pintype "bidirectional"))
      (node (ref "HT16K6") (pin "P$27") (pinfunction "SDA_P$27") (pintype "bidirectional"))
      (node (ref "HT16K7") (pin "P$27") (pinfunction "SDA_P$27") (pintype "bidirectional"))
      (node (ref "HT16K8") (pin "P$27") (pinfunction "SDA_P$27") (pintype "bidirectional"))
      (node (ref "J1") (pin "2") (pinfunction "2_2") (pintype "passive"))
      (node (ref "R12") (pin "2") (pinfunction "2_2") (pintype "passive"))
      (node (ref "R17") (pin "2") (pinfunction "2_2") (pintype "passive"))
      (node (ref "R19") (pin "2") (pinfunction "2_2") (pintype "passive"))
      (node (ref "R27") (pin "2") (pinfunction "2_2") (pintype "passive"))
      (node (ref "R32") (pin "2") (pinfunction "2_2") (pintype "passive"))
      (node (ref "R37") (pin "2") (pinfunction "2_2") (pintype "passive"))
      (node (ref "R42") (pin "2") (pinfunction "2_2") (pintype "passive"))
      (node (ref "R7") (pin "2") (pinfunction "2_2") (pintype "passive"))
    )
    (net (code "27") (name "GND") (class "Default")
      (node (ref "HT16K2") (pin "P$1") (pinfunction "VSS_P$1") (pintype "bidirectional"))
      (node (ref "HT16K3") (pin "P$1") (pinfunction "VSS_P$1") (pintype "bidirectional"))
      (node (ref "HT16K33") (pin "P$1") (pinfunction "VSS_P$1") (pintype "bidirectional"))
      (node (ref "HT16K4") (pin "P$1") (pinfunction "VSS_P$1") (pintype "bidirectional"))
      (node (ref "HT16K5") (pin "P$1") (pinfunction "VSS_P$1") (pintype "bidirectional"))
      (node (ref "HT16K6") (pin "P$1") (pinfunction "VSS_P$1") (pintype "bidirectional"))
      (node (ref "HT16K7") (pin "P$1") (pinfunction "VSS_P$1") (pintype "bidirectional"))
      (node (ref "HT16K8") (pin "P$1") (pinfunction "VSS_P$1") (pintype "bidirectional"))
      (node (ref "J1") (pin "4") (pinfunction "4_4") (pintype "passive"))
      (node (ref "J2") (pin "1") (pinfunction "1_1") (pintype "passive"))
    )
    (net (code "28") (name "Net-(D1-PadC)") (class "Default")
      (node (ref "D1") (pin "C") (pinfunction "C_C") (pintype "passive"))
      (node (ref "R20") (pin "1") (pinfunction "1_1") (pintype "passive"))
      (node (ref "R21") (pin "1") (pinfunction "1_1") (pintype "passive"))
      (node (ref "R22") (pin "1") (pinfunction "1_1") (pintype "passive"))
    )
    (net (code "29") (name "Net-(D3-PadC)") (class "Default")
      (node (ref "D3") (pin "C") (pinfunction "C_C") (pintype "passive"))
      (node (ref "R10") (pin "1") (pinfunction "1_1") (pintype "passive"))
      (node (ref "R8") (pin "1") (pinfunction "1_1") (pintype "passive"))
      (node (ref "R9") (pin "1") (pinfunction "1_1") (pintype "passive"))
    )
    (net (code "30") (name "Net-(D4-PadC)") (class "Default")
      (node (ref "D4") (pin "C") (pinfunction "C_C") (pintype "passive"))
      (node (ref "R13") (pin "1") (pinfunction "1_1") (pintype "passive"))
      (node (ref "R14") (pin "1") (pinfunction "1_1") (pintype "passive"))
      (node (ref "R15") (pin "1") (pinfunction "1_1") (pintype "passive"))
    )
    (net (code "31") (name "Net-(D5-PadC)") (class "Default")
      (node (ref "D5") (pin "C") (pinfunction "C_C") (pintype "passive"))
      (node (ref "R23") (pin "1") (pinfunction "1_1") (pintype "passive"))
      (node (ref "R24") (pin "1") (pinfunction "1_1") (pintype "passive"))
      (node (ref "R25") (pin "1") (pinfunction "1_1") (pintype "passive"))
    )
    (net (code "32") (name "Net-(D6-PadC)") (class "Default")
      (node (ref "D6") (pin "C") (pinfunction "C_C") (pintype "passive"))
      (node (ref "R28") (pin "1") (pinfunction "1_1") (pintype "passive"))
      (node (ref "R29") (pin "1") (pinfunction "1_1") (pintype "passive"))
      (node (ref "R30") (pin "1") (pinfunction "1_1") (pintype "passive"))
    )
    (net (code "33") (name "Net-(D7-PadC)") (class "Default")
      (node (ref "D7") (pin "C") (pinfunction "C_C") (pintype "passive"))
      (node (ref "R33") (pin "1") (pinfunction "1_1") (pintype "passive"))
      (node (ref "R34") (pin "1") (pinfunction "1_1") (pintype "passive"))
      (node (ref "R35") (pin "1") (pinfunction "1_1") (pintype "passive"))
    )
    (net (code "34") (name "Net-(D8-PadC)") (class "Default")
      (node (ref "D8") (pin "C") (pinfunction "C_C") (pintype "passive"))
      (node (ref "R38") (pin "1") (pinfunction "1_1") (pintype "passive"))
      (node (ref "R39") (pin "1") (pinfunction "1_1") (pintype "passive"))
      (node (ref "R40") (pin "1") (pinfunction "1_1") (pintype "passive"))
    )
    (net (code "35") (name "Net-(D9-PadC)") (class "Default")
      (node (ref "D9") (pin "C") (pinfunction "C_C") (pintype "passive"))
      (node (ref "R43") (pin "1") (pinfunction "1_1") (pintype "passive"))
      (node (ref "R44") (pin "1") (pinfunction "1_1") (pintype "passive"))
      (node (ref "R45") (pin "1") (pinfunction "1_1") (pintype "passive"))
    )
    (net (code "36") (name "Net-(HT16K2-COM0{slash}AD)") (class "Default")
      (node (ref "D3") (pin "A") (pinfunction "A_A") (pintype "passive"))
      (node (ref "HT16K2") (pin "P$2") (pinfunction "COM0/AD_P$2") (pintype "bidirectional"))
      (node (ref "U$11") (pin "16") (pinfunction "COM1_16") (pintype "bidirectional"))
    )
    (net (code "37") (name "Net-(HT16K2-COM1{slash}KS0)") (class "Default")
      (node (ref "HT16K2") (pin "P$3") (pinfunction "COM1/KS0_P$3") (pintype "bidirectional"))
      (node (ref "U$11") (pin "11") (pinfunction "COM2_11") (pintype "bidirectional"))
    )
    (net (code "38") (name "Net-(HT16K2-COM2{slash}KS1)") (class "Default")
      (node (ref "HT16K2") (pin "P$4") (pinfunction "COM2/KS1_P$4") (pintype "bidirectional"))
      (node (ref "U$12") (pin "16") (pinfunction "COM1_16") (pintype "bidirectional"))
    )
    (net (code "39") (name "Net-(HT16K2-COM3{slash}KS2)") (class "Default")
      (node (ref "HT16K2") (pin "P$5") (pinfunction "COM3/KS2_P$5") (pintype "bidirectional"))
      (node (ref "U$12") (pin "11") (pinfunction "COM2_11") (pintype "bidirectional"))
    )
    (net (code "40") (name "Net-(HT16K2-COM4)") (class "Default")
      (node (ref "HT16K2") (pin "P$6") (pinfunction "COM4_P$6") (pintype "bidirectional"))
      (node (ref "U$13") (pin "16") (pinfunction "COM1_16") (pintype "bidirectional"))
    )
    (net (code "41") (name "Net-(HT16K2-COM5)") (class "Default")
      (node (ref "HT16K2") (pin "P$7") (pinfunction "COM5_P$7") (pintype "bidirectional"))
      (node (ref "U$13") (pin "11") (pinfunction "COM2_11") (pintype "bidirectional"))
    )
    (net (code "42") (name "Net-(HT16K2-COM6)") (class "Default")
      (node (ref "HT16K2") (pin "P$8") (pinfunction "COM6_P$8") (pintype "bidirectional"))
      (node (ref "U$14") (pin "16") (pinfunction "COM1_16") (pintype "bidirectional"))
    )
    (net (code "43") (name "Net-(HT16K2-COM7)") (class "Default")
      (node (ref "HT16K2") (pin "P$9") (pinfunction "COM7_P$9") (pintype "bidirectional"))
      (node (ref "U$14") (pin "11") (pinfunction "COM2_11") (pintype "bidirectional"))
    )
    (net (code "44") (name "Net-(HT16K2-ROW3{slash}K1)") (class "Default")
      (node (ref "HT16K2") (pin "P$22") (pinfunction "ROW3/K1_P$22") (pintype "bidirectional"))
      (node (ref "U$11") (pin "7") (pinfunction "D_7") (pintype "bidirectional"))
      (node (ref "U$12") (pin "7") (pinfunction "D_7") (pintype "bidirectional"))
      (node (ref "U$13") (pin "7") (pinfunction "D_7") (pintype "bidirectional"))
      (node (ref "U$14") (pin "7") (pinfunction "D_7") (pintype "bidirectional"))
    )
    (net (code "45") (name "Net-(HT16K2-ROW4{slash}K2)") (class "Default")
      (node (ref "HT16K2") (pin "P$21") (pinfunction "ROW4/K2_P$21") (pintype "bidirectional"))
      (node (ref "U$11") (pin "1") (pinfunction "E_1") (pintype "bidirectional"))
      (node (ref "U$12") (pin "1") (pinfunction "E_1") (pintype "bidirectional"))
      (node (ref "U$13") (pin "1") (pinfunction "E_1") (pintype "bidirectional"))
      (node (ref "U$14") (pin "1") (pinfunction "E_1") (pintype "bidirectional"))
    )
    (net (code "46") (name "Net-(HT16K2-ROW5{slash}K3)") (class "Default")
      (node (ref "HT16K2") (pin "P$20") (pinfunction "ROW5/K3_P$20") (pintype "bidirectional"))
      (node (ref "U$11") (pin "18") (pinfunction "F_18") (pintype "bidirectional"))
      (node (ref "U$12") (pin "18") (pinfunction "F_18") (pintype "bidirectional"))
      (node (ref "U$13") (pin "18") (pinfunction "F_18") (pintype "bidirectional"))
      (node (ref "U$14") (pin "18") (pinfunction "F_18") (pintype "bidirectional"))
    )
    (net (code "47") (name "Net-(HT16K2-ROW6{slash}K4)") (class "Default")
      (node (ref "HT16K2") (pin "P$19") (pinfunction "ROW6/K4_P$19") (pintype "bidirectional"))
      (node (ref "U$11") (pin "13") (pinfunction "N_13") (pintype "bidirectional"))
      (node (ref "U$12") (pin "13") (pinfunction "N_13") (pintype "bidirectional"))
      (node (ref "U$13") (pin "13") (pinfunction "N_13") (pintype "bidirectional"))
      (node (ref "U$14") (pin "13") (pinfunction "N_13") (pintype "bidirectional"))
    )
    (net (code "48") (name "Net-(HT16K2-ROW7{slash}K5)") (class "Default")
      (node (ref "HT16K2") (pin "P$18") (pinfunction "ROW7/K5_P$18") (pintype "bidirectional"))
      (node (ref "U$11") (pin "6") (pinfunction "J_6") (pintype "bidirectional"))
      (node (ref "U$12") (pin "6") (pinfunction "J_6") (pintype "bidirectional"))
      (node (ref "U$13") (pin "6") (pinfunction "J_6") (pintype "bidirectional"))
      (node (ref "U$14") (pin "6") (pinfunction "J_6") (pintype "bidirectional"))
    )
    (net (code "49") (name "Net-(HT16K2-ROW8{slash}K6)") (class "Default")
      (node (ref "HT16K2") (pin "P$17") (pinfunction "ROW8/K6_P$17") (pintype "bidirectional"))
      (node (ref "U$11") (pin "17") (pinfunction "P_17") (pintype "bidirectional"))
      (node (ref "U$12") (pin "17") (pinfunction "P_17") (pintype "bidirectional"))
      (node (ref "U$13") (pin "17") (pinfunction "P_17") (pintype "bidirectional"))
      (node (ref "U$14") (pin "17") (pinfunction "P_17") (pintype "bidirectional"))
    )
    (net (code "50") (name "Net-(HT16K2-ROW9{slash}K7)") (class "Default")
      (node (ref "HT16K2") (pin "P$16") (pinfunction "ROW9/K7_P$16") (pintype "bidirectional"))
      (node (ref "U$11") (pin "15") (pinfunction "G_15") (pintype "bidirectional"))
      (node (ref "U$12") (pin "15") (pinfunction "G_15") (pintype "bidirectional"))
      (node (ref "U$13") (pin "15") (pinfunction "G_15") (pintype "bidirectional"))
      (node (ref "U$14") (pin "15") (pinfunction "G_15") (pintype "bidirectional"))
    )
    (net (code "51") (name "Net-(HT16K2-ROW10{slash}K8)") (class "Default")
      (node (ref "HT16K2") (pin "P$15") (pinfunction "ROW10/K8_P$15") (pintype "bidirectional"))
      (node (ref "U$11") (pin "14") (pinfunction "H_14") (pintype "bidirectional"))
      (node (ref "U$12") (pin "14") (pinfunction "H_14") (pintype "bidirectional"))
      (node (ref "U$13") (pin "14") (pinfunction "H_14") (pintype "bidirectional"))
      (node (ref "U$14") (pin "14") (pinfunction "H_14") (pintype "bidirectional"))
    )
    (net (code "52") (name "Net-(HT16K2-ROW11{slash}K9)") (class "Default")
      (node (ref "HT16K2") (pin "P$14") (pinfunction "ROW11/K9_P$14") (pintype "bidirectional"))
      (node (ref "U$11") (pin "2") (pinfunction "M_2") (pintype "bidirectional"))
      (node (ref "U$12") (pin "2") (pinfunction "M_2") (pintype "bidirectional"))
      (node (ref "U$13") (pin "2") (pinfunction "M_2") (pintype "bidirectional"))
      (node (ref "U$14") (pin "2") (pinfunction "M_2") (pintype "bidirectional"))
    )
    (net (code "53") (name "Net-(HT16K2-ROW12{slash}K10)") (class "Default")
      (node (ref "HT16K2") (pin "P$13") (pinfunction "ROW12/K10_P$13") (pintype "bidirectional"))
      (node (ref "U$11") (pin "4") (pinfunction "L_4") (pintype "bidirectional"))
      (node (ref "U$12") (pin "4") (pinfunction "L_4") (pintype "bidirectional"))
      (node (ref "U$13") (pin "4") (pinfunction "L_4") (pintype "bidirectional"))
      (node (ref "U$14") (pin "4") (pinfunction "L_4") (pintype "bidirectional"))
    )
    (net (code "54") (name "Net-(HT16K2-ROW13{slash}K11)") (class "Default")
      (node (ref "HT16K2") (pin "P$12") (pinfunction "ROW13/K11_P$12") (pintype "bidirectional"))
      (node (ref "U$11") (pin "5") (pinfunction "K_5") (pintype "bidirectional"))
      (node (ref "U$12") (pin "5") (pinfunction "K_5") (pintype "bidirectional"))
      (node (ref "U$13") (pin "5") (pinfunction "K_5") (pintype "bidirectional"))
      (node (ref "U$14") (pin "5") (pinfunction "K_5") (pintype "bidirectional"))
    )
    (net (code "55") (name "Net-(HT16K2-ROW14{slash}K12)") (class "Default")
      (node (ref "HT16K2") (pin "P$11") (pinfunction "ROW14/K12_P$11") (pintype "bidirectional"))
      (node (ref "U$11") (pin "8") (pinfunction "DP_8") (pintype "bidirectional"))
      (node (ref "U$12") (pin "8") (pinfunction "DP_8") (pintype "bidirectional"))
      (node (ref "U$13") (pin "8") (pinfunction "DP_8") (pintype "bidirectional"))
      (node (ref "U$14") (pin "8") (pinfunction "DP_8") (pintype "bidirectional"))
    )
    (net (code "56") (name "Net-(HT16K3-COM0{slash}AD)") (class "Default")
      (node (ref "D4") (pin "A") (pinfunction "A_A") (pintype "passive"))
      (node (ref "HT16K3") (pin "P$2") (pinfunction "COM0/AD_P$2") (pintype "bidirectional"))
      (node (ref "U$15") (pin "16") (pinfunction "COM1_16") (pintype "bidirectional"))
    )
    (net (code "57") (name "Net-(HT16K3-COM1{slash}KS0)") (class "Default")
      (node (ref "HT16K3") (pin "P$3") (pinfunction "COM1/KS0_P$3") (pintype "bidirectional"))
      (node (ref "U$15") (pin "11") (pinfunction "COM2_11") (pintype "bidirectional"))
    )
    (net (code "58") (name "Net-(HT16K3-COM2{slash}KS1)") (class "Default")
      (node (ref "HT16K3") (pin "P$4") (pinfunction "COM2/KS1_P$4") (pintype "bidirectional"))
      (node (ref "U$16") (pin "16") (pinfunction "COM1_16") (pintype "bidirectional"))
    )
    (net (code "59") (name "Net-(HT16K3-COM3{slash}KS2)") (class "Default")
      (node (ref "HT16K3") (pin "P$5") (pinfunction "COM3/KS2_P$5") (pintype "bidirectional"))
      (node (ref "U$16") (pin "11") (pinfunction "COM2_11") (pintype "bidirectional"))
    )
    (net (code "60") (name "Net-(HT16K3-COM4)") (class "Default")
      (node (ref "HT16K3") (pin "P$6") (pinfunction "COM4_P$6") (pintype "bidirectional"))
      (node (ref "U$17") (pin "16") (pinfunction "COM1_16") (pintype "bidirectional"))
    )
    (net (code "61") (name "Net-(HT16K3-COM5)") (class "Default")
      (node (ref "HT16K3") (pin "P$7") (pinfunction "COM5_P$7") (pintype "bidirectional"))
      (node (ref "U$17") (pin "11") (pinfunction "COM2_11") (pintype "bidirectional"))
    )
    (net (code "62") (name "Net-(HT16K3-COM6)") (class "Default")
      (node (ref "HT16K3") (pin "P$8") (pinfunction "COM6_P$8") (pintype "bidirectional"))
      (node (ref "U$18") (pin "16") (pinfunction "COM1_16") (pintype "bidirectional"))
    )
    (net (code "63") (name "Net-(HT16K3-COM7)") (class "Default")
      (node (ref "HT16K3") (pin "P$9") (pinfunction "COM7_P$9") (pintype "bidirectional"))
      (node (ref "U$18") (pin "11") (pinfunction "COM2_11") (pintype "bidirectional"))
    )
    (net (code "64") (name "Net-(HT16K3-ROW3{slash}K1)") (class "Default")
      (node (ref "HT16K3") (pin "P$22") (pinfunction "ROW3/K1_P$22") (pintype "bidirectional"))
      (node (ref "U$15") (pin "7") (pinfunction "D_7") (pintype "bidirectional"))
      (node (ref "U$16") (pin "7") (pinfunction "D_7") (pintype "bidirectional"))
      (node (ref "U$17") (pin "7") (pinfunction "D_7") (pintype "bidirectional"))
      (node (ref "U$18") (pin "7") (pinfunction "D_7") (pintype "bidirectional"))
    )
    (net (code "65") (name "Net-(HT16K3-ROW4{slash}K2)") (class "Default")
      (node (ref "HT16K3") (pin "P$21") (pinfunction "ROW4/K2_P$21") (pintype "bidirectional"))
      (node (ref "U$15") (pin "1") (pinfunction "E_1") (pintype "bidirectional"))
      (node (ref "U$16") (pin "1") (pinfunction "E_1") (pintype "bidirectional"))
      (node (ref "U$17") (pin "1") (pinfunction "E_1") (pintype "bidirectional"))
      (node (ref "U$18") (pin "1") (pinfunction "E_1") (pintype "bidirectional"))
    )
    (net (code "66") (name "Net-(HT16K3-ROW5{slash}K3)") (class "Default")
      (node (ref "HT16K3") (pin "P$20") (pinfunction "ROW5/K3_P$20") (pintype "bidirectional"))
      (node (ref "U$15") (pin "18") (pinfunction "F_18") (pintype "bidirectional"))
      (node (ref "U$16") (pin "18") (pinfunction "F_18") (pintype "bidirectional"))
      (node (ref "U$17") (pin "18") (pinfunction "F_18") (pintype "bidirectional"))
      (node (ref "U$18") (pin "18") (pinfunction "F_18") (pintype "bidirectional"))
    )
    (net (code "67") (name "Net-(HT16K3-ROW6{slash}K4)") (class "Default")
      (node (ref "HT16K3") (pin "P$19") (pinfunction "ROW6/K4_P$19") (pintype "bidirectional"))
      (node (ref "U$15") (pin "13") (pinfunction "N_13") (pintype "bidirectional"))
      (node (ref "U$16") (pin "13") (pinfunction "N_13") (pintype "bidirectional"))
      (node (ref "U$17") (pin "13") (pinfunction "N_13") (pintype "bidirectional"))
      (node (ref "U$18") (pin "13") (pinfunction "N_13") (pintype "bidirectional"))
    )
    (net (code "68") (name "Net-(HT16K3-ROW7{slash}K5)") (class "Default")
      (node (ref "HT16K3") (pin "P$18") (pinfunction "ROW7/K5_P$18") (pintype "bidirectional"))
      (node (ref "U$15") (pin "6") (pinfunction "J_6") (pintype "bidirectional"))
      (node (ref "U$16") (pin "6") (pinfunction "J_6") (pintype "bidirectional"))
      (node (ref "U$17") (pin "6") (pinfunction "J_6") (pintype "bidirectional"))
      (node (ref "U$18") (pin "6") (pinfunction "J_6") (pintype "bidirectional"))
    )
    (net (code "69") (name "Net-(HT16K3-ROW8{slash}K6)") (class "Default")
      (node (ref "HT16K3") (pin "P$17") (pinfunction "ROW8/K6_P$17") (pintype "bidirectional"))
      (node (ref "U$15") (pin "17") (pinfunction "P_17") (pintype "bidirectional"))
      (node (ref "U$16") (pin "17") (pinfunction "P_17") (pintype "bidirectional"))
      (node (ref "U$17") (pin "17") (pinfunction "P_17") (pintype "bidirectional"))
      (node (ref "U$18") (pin "17") (pinfunction "P_17") (pintype "bidirectional"))
    )
    (net (code "70") (name "Net-(HT16K3-ROW9{slash}K7)") (class "Default")
      (node (ref "HT16K3") (pin "P$16") (pinfunction "ROW9/K7_P$16") (pintype "bidirectional"))
      (node (ref "U$15") (pin "15") (pinfunction "G_15") (pintype "bidirectional"))
      (node (ref "U$16") (pin "15") (pinfunction "G_15") (pintype "bidirectional"))
      (node (ref "U$17") (pin "15") (pinfunction "G_15") (pintype "bidirectional"))
      (node (ref "U$18") (pin "15") (pinfunction "G_15") (pintype "bidirectional"))
    )
    (net (code "71") (name "Net-(HT16K3-ROW10{slash}K8)") (class "Default")
      (node (ref "HT16K3") (pin "P$15") (pinfunction "ROW10/K8_P$15") (pintype "bidirectional"))
      (node (ref "U$15") (pin "14") (pinfunction "H_14") (pintype "bidirectional"))
      (node (ref "U$16") (pin "14") (pinfunction "H_14") (pintype "bidirectional"))
      (node (ref "U$17") (pin "14") (pinfunction "H_14") (pintype "bidirectional"))
      (node (ref "U$18") (pin "14") (pinfunction "H_14") (pintype "bidirectional"))
    )
    (net (code "72") (name "Net-(HT16K3-ROW11{slash}K9)") (class "Default")
      (node (ref "HT16K3") (pin "P$14") (pinfunction "ROW11/K9_P$14") (pintype "bidirectional"))
      (node (ref "U$15") (pin "2") (pinfunction "M_2") (pintype "bidirectional"))
      (node (ref "U$16") (pin "2") (pinfunction "M_2") (pintype "bidirectional"))
      (node (ref "U$17") (pin "2") (pinfunction "M_2") (pintype "bidirectional"))
      (node (ref "U$18") (pin "2") (pinfunction "M_2") (pintype "bidirectional"))
    )
    (net (code "73") (name "Net-(HT16K3-ROW12{slash}K10)") (class "Default")
      (node (ref "HT16K3") (pin "P$13") (pinfunction "ROW12/K10_P$13") (pintype "bidirectional"))
      (node (ref "U$15") (pin "4") (pinfunction "L_4") (pintype "bidirectional"))
      (node (ref "U$16") (pin "4") (pinfunction "L_4") (pintype "bidirectional"))
      (node (ref "U$17") (pin "4") (pinfunction "L_4") (pintype "bidirectional"))
      (node (ref "U$18") (pin "4") (pinfunction "L_4") (pintype "bidirectional"))
    )
    (net (code "74") (name "Net-(HT16K3-ROW13{slash}K11)") (class "Default")
      (node (ref "HT16K3") (pin "P$12") (pinfunction "ROW13/K11_P$12") (pintype "bidirectional"))
      (node (ref "U$15") (pin "5") (pinfunction "K_5") (pintype "bidirectional"))
      (node (ref "U$16") (pin "5") (pinfunction "K_5") (pintype "bidirectional"))
      (node (ref "U$17") (pin "5") (pinfunction "K_5") (pintype "bidirectional"))
      (node (ref "U$18") (pin "5") (pinfunction "K_5") (pintype "bidirectional"))
    )
    (net (code "75") (name "Net-(HT16K3-ROW14{slash}K12)") (class "Default")
      (node (ref "HT16K3") (pin "P$11") (pinfunction "ROW14/K12_P$11") (pintype "bidirectional"))
      (node (ref "U$15") (pin "8") (pinfunction "DP_8") (pintype "bidirectional"))
      (node (ref "U$16") (pin "8") (pinfunction "DP_8") (pintype "bidirectional"))
      (node (ref "U$17") (pin "8") (pinfunction "DP_8") (pintype "bidirectional"))
      (node (ref "U$18") (pin "8") (pinfunction "DP_8") (pintype "bidirectional"))
    )
    (net (code "76") (name "Net-(HT16K4-COM0{slash}AD)") (class "Default")
      (node (ref "D5") (pin "A") (pinfunction "A_A") (pintype "passive"))
      (node (ref "HT16K4") (pin "P$2") (pinfunction "COM0/AD_P$2") (pintype "bidirectional"))
      (node (ref "U$19") (pin "16") (pinfunction "COM1_16") (pintype "bidirectional"))
    )
    (net (code "77") (name "Net-(HT16K4-COM1{slash}KS0)") (class "Default")
      (node (ref "HT16K4") (pin "P$3") (pinfunction "COM1/KS0_P$3") (pintype "bidirectional"))
      (node (ref "U$19") (pin "11") (pinfunction "COM2_11") (pintype "bidirectional"))
    )
    (net (code "78") (name "Net-(HT16K4-COM2{slash}KS1)") (class "Default")
      (node (ref "HT16K4") (pin "P$4") (pinfunction "COM2/KS1_P$4") (pintype "bidirectional"))
      (node (ref "U$20") (pin "16") (pinfunction "COM1_16") (pintype "bidirectional"))
    )
    (net (code "79") (name "Net-(HT16K4-COM3{slash}KS2)") (class "Default")
      (node (ref "HT16K4") (pin "P$5") (pinfunction "COM3/KS2_P$5") (pintype "bidirectional"))
      (node (ref "U$20") (pin "11") (pinfunction "COM2_11") (pintype "bidirectional"))
    )
    (net (code "80") (name "Net-(HT16K4-COM4)") (class "Default")
      (node (ref "HT16K4") (pin "P$6") (pinfunction "COM4_P$6") (pintype "bidirectional"))
      (node (ref "U$21") (pin "16") (pinfunction "COM1_16") (pintype "bidirectional"))
    )
    (net (code "81") (name "Net-(HT16K4-COM5)") (class "Default")
      (node (ref "HT16K4") (pin "P$7") (pinfunction "COM5_P$7") (pintype "bidirectional"))
      (node (ref "U$21") (pin "11") (pinfunction "COM2_11") (pintype "bidirectional"))
    )
    (net (code "82") (name "Net-(HT16K4-COM6)") (class "Default")
      (node (ref "HT16K4") (pin "P$8") (pinfunction "COM6_P$8") (pintype "bidirectional"))
      (node (ref "U$22") (pin "16") (pinfunction "COM1_16") (pintype "bidirectional"))
    )
    (net (code "83") (name "Net-(HT16K4-COM7)") (class "Default")
      (node (ref "HT16K4") (pin "P$9") (pinfunction "COM7_P$9") (pintype "bidirectional"))
      (node (ref "U$22") (pin "11") (pinfunction "COM2_11") (pintype "bidirectional"))
    )
    (net (code "84") (name "Net-(HT16K4-ROW3{slash}K1)") (class "Default")
      (node (ref "HT16K4") (pin "P$22") (pinfunction "ROW3/K1_P$22") (pintype "bidirectional"))
      (node (ref "U$19") (pin "7") (pinfunction "D_7") (pintype "bidirectional"))
      (node (ref "U$20") (pin "7") (pinfunction "D_7") (pintype "bidirectional"))
      (node (ref "U$21") (pin "7") (pinfunction "D_7") (pintype "bidirectional"))
      (node (ref "U$22") (pin "7") (pinfunction "D_7") (pintype "bidirectional"))
    )
    (net (code "85") (name "Net-(HT16K4-ROW4{slash}K2)") (class "Default")
      (node (ref "HT16K4") (pin "P$21") (pinfunction "ROW4/K2_P$21") (pintype "bidirectional"))
      (node (ref "U$19") (pin "1") (pinfunction "E_1") (pintype "bidirectional"))
      (node (ref "U$20") (pin "1") (pinfunction "E_1") (pintype "bidirectional"))
      (node (ref "U$21") (pin "1") (pinfunction "E_1") (pintype "bidirectional"))
      (node (ref "U$22") (pin "1") (pinfunction "E_1") (pintype "bidirectional"))
    )
    (net (code "86") (name "Net-(HT16K4-ROW5{slash}K3)") (class "Default")
      (node (ref "HT16K4") (pin "P$20") (pinfunction "ROW5/K3_P$20") (pintype "bidirectional"))
      (node (ref "U$19") (pin "18") (pinfunction "F_18") (pintype "bidirectional"))
      (node (ref "U$20") (pin "18") (pinfunction "F_18") (pintype "bidirectional"))
      (node (ref "U$21") (pin "18") (pinfunction "F_18") (pintype "bidirectional"))
      (node (ref "U$22") (pin "18") (pinfunction "F_18") (pintype "bidirectional"))
    )
    (net (code "87") (name "Net-(HT16K4-ROW6{slash}K4)") (class "Default")
      (node (ref "HT16K4") (pin "P$19") (pinfunction "ROW6/K4_P$19") (pintype "bidirectional"))
      (node (ref "U$19") (pin "13") (pinfunction "N_13") (pintype "bidirectional"))
      (node (ref "U$20") (pin "13") (pinfunction "N_13") (pintype "bidirectional"))
      (node (ref "U$21") (pin "13") (pinfunction "N_13") (pintype "bidirectional"))
      (node (ref "U$22") (pin "13") (pinfunction "N_13") (pintype "bidirectional"))
    )
    (net (code "88") (name "Net-(HT16K4-ROW7{slash}K5)") (class "Default")
      (node (ref "HT16K4") (pin "P$18") (pinfunction "ROW7/K5_P$18") (pintype "bidirectional"))
      (node (ref "U$19") (pin "6") (pinfunction "J_6") (pintype "bidirectional"))
      (node (ref "U$20") (pin "6") (pinfunction "J_6") (pintype "bidirectional"))
      (node (ref "U$21") (pin "6") (pinfunction "J_6") (pintype "bidirectional"))
      (node (ref "U$22") (pin "6") (pinfunction "J_6") (pintype "bidirectional"))
    )
    (net (code "89") (name "Net-(HT16K4-ROW8{slash}K6)") (class "Default")
      (node (ref "HT16K4") (pin "P$17") (pinfunction "ROW8/K6_P$17") (pintype "bidirectional"))
      (node (ref "U$19") (pin "17") (pinfunction "P_17") (pintype "bidirectional"))
      (node (ref "U$20") (pin "17") (pinfunction "P_17") (pintype "bidirectional"))
      (node (ref "U$21") (pin "17") (pinfunction "P_17") (pintype "bidirectional"))
      (node (ref "U$22") (pin "17") (pinfunction "P_17") (pintype "bidirectional"))
    )
    (net (code "90") (name "Net-(HT16K4-ROW9{slash}K7)") (class "Default")
      (node (ref "HT16K4") (pin "P$16") (pinfunction "ROW9/K7_P$16") (pintype "bidirectional"))
      (node (ref "U$19") (pin "15") (pinfunction "G_15") (pintype "bidirectional"))
      (node (ref "U$20") (pin "15") (pinfunction "G_15") (pintype "bidirectional"))
      (node (ref "U$21") (pin "15") (pinfunction "G_15") (pintype "bidirectional"))
      (node (ref "U$22") (pin "15") (pinfunction "G_15") (pintype "bidirectional"))
    )
    (net (code "91") (name "Net-(HT16K4-ROW10{slash}K8)") (class "Default")
      (node (ref "HT16K4") (pin "P$15") (pinfunction "ROW10/K8_P$15") (pintype "bidirectional"))
      (node (ref "U$19") (pin "14") (pinfunction "H_14") (pintype "bidirectional"))
      (node (ref "U$20") (pin "14") (pinfunction "H_14") (pintype "bidirectional"))
      (node (ref "U$21") (pin "14") (pinfunction "H_14") (pintype "bidirectional"))
      (node (ref "U$22") (pin "14") (pinfunction "H_14") (pintype "bidirectional"))
    )
    (net (code "92") (name "Net-(HT16K4-ROW11{slash}K9)") (class "Default")
      (node (ref "HT16K4") (pin "P$14") (pinfunction "ROW11/K9_P$14") (pintype "bidirectional"))
      (node (ref "U$19") (pin "2") (pinfunction "M_2") (pintype "bidirectional"))
      (node (ref "U$20") (pin "2") (pinfunction "M_2") (pintype "bidirectional"))
      (node (ref "U$21") (pin "2") (pinfunction "M_2") (pintype "bidirectional"))
      (node (ref "U$22") (pin "2") (pinfunction "M_2") (pintype "bidirectional"))
    )
    (net (code "93") (name "Net-(HT16K4-ROW12{slash}K10)") (class "Default")
      (node (ref "HT16K4") (pin "P$13") (pinfunction "ROW12/K10_P$13") (pintype "bidirectional"))
      (node (ref "U$19") (pin "4") (pinfunction "L_4") (pintype "bidirectional"))
      (node (ref "U$20") (pin "4") (pinfunction "L_4") (pintype "bidirectional"))
      (node (ref "U$21") (pin "4") (pinfunction "L_4") (pintype "bidirectional"))
      (node (ref "U$22") (pin "4") (pinfunction "L_4") (pintype "bidirectional"))
    )
    (net (code "94") (name "Net-(HT16K4-ROW13{slash}K11)") (class "Default")
      (node (ref "HT16K4") (pin "P$12") (pinfunction "ROW13/K11_P$12") (pintype "bidirectional"))
      (node (ref "U$19") (pin "5") (pinfunction "K_5") (pintype "bidirectional"))
      (node (ref "U$20") (pin "5") (pinfunction "K_5") (pintype "bidirectional"))
      (node (ref "U$21") (pin "5") (pinfunction "K_5") (pintype "bidirectional"))
      (node (ref "U$22") (pin "5") (pinfunction "K_5") (pintype "bidirectional"))
    )
    (net (code "95") (name "Net-(HT16K4-ROW14{slash}K12)") (class "Default")
      (node (ref "HT16K4") (pin "P$11") (pinfunction "ROW14/K12_P$11") (pintype "bidirectional"))
      (node (ref "U$19") (pin "8") (pinfunction "DP_8") (pintype "bidirectional"))
      (node (ref "U$20") (pin "8") (pinfunction "DP_8") (pintype "bidirectional"))
      (node (ref "U$21") (pin "8") (pinfunction "DP_8") (pintype "bidirectional"))
      (node (ref "U$22") (pin "8") (pinfunction "DP_8") (pintype "bidirectional"))
    )
    (net (code "96") (name "Net-(HT16K5-COM0{slash}AD)") (class "Default")
      (node (ref "D6") (pin "A") (pinfunction "A_A") (pintype "passive"))
      (node (ref "HT16K5") (pin "P$2") (pinfunction "COM0/AD_P$2") (pintype "bidirectional"))
      (node (ref "U$23") (pin "16") (pinfunction "COM1_16") (pintype "bidirectional"))
    )
    (net (code "97") (name "Net-(HT16K5-COM1{slash}KS0)") (class "Default")
      (node (ref "HT16K5") (pin "P$3") (pinfunction "COM1/KS0_P$3") (pintype "bidirectional"))
      (node (ref "U$23") (pin "11") (pinfunction "COM2_11") (pintype "bidirectional"))
    )
    (net (code "98") (name "Net-(HT16K5-COM2{slash}KS1)") (class "Default")
      (node (ref "HT16K5") (pin "P$4") (pinfunction "COM2/KS1_P$4") (pintype "bidirectional"))
      (node (ref "U$24") (pin "16") (pinfunction "COM1_16") (pintype "bidirectional"))
    )
    (net (code "99") (name "Net-(HT16K5-COM3{slash}KS2)") (class "Default")
      (node (ref "HT16K5") (pin "P$5") (pinfunction "COM3/KS2_P$5") (pintype "bidirectional"))
      (node (ref "U$24") (pin "11") (pinfunction "COM2_11") (pintype "bidirectional"))
    )
    (net (code "100") (name "Net-(HT16K5-COM4)") (class "Default")
      (node (ref "HT16K5") (pin "P$6") (pinfunction "COM4_P$6") (pintype "bidirectional"))
      (node (ref "U$25") (pin "16") (pinfunction "COM1_16") (pintype "bidirectional"))
    )
    (net (code "101") (name "Net-(HT16K5-COM5)") (class "Default")
      (node (ref "HT16K5") (pin "P$7") (pinfunction "COM5_P$7") (pintype "bidirectional"))
      (node (ref "U$25") (pin "11") (pinfunction "COM2_11") (pintype "bidirectional"))
    )
    (net (code "102") (name "Net-(HT16K5-COM6)") (class "Default")
      (node (ref "HT16K5") (pin "P$8") (pinfunction "COM6_P$8") (pintype "bidirectional"))
      (node (ref "U$26") (pin "16") (pinfunction "COM1_16") (pintype "bidirectional"))
    )
    (net (code "103") (name "Net-(HT16K5-COM7)") (class "Default")
      (node (ref "HT16K5") (pin "P$9") (pinfunction "COM7_P$9") (pintype "bidirectional"))
      (node (ref "U$26") (pin "11") (pinfunction "COM2_11") (pintype "bidirectional"))
    )
    (net (code "104") (name "Net-(HT16K5-ROW3{slash}K1)") (class "Default")
      (node (ref "HT16K5") (pin "P$22") (pinfunction "ROW3/K1_P$22") (pintype "bidirectional"))
      (node (ref "U$23") (pin "7") (pinfunction "D_7") (pintype "bidirectional"))
      (node (ref "U$24") (pin "7") (pinfunction "D_7") (pintype "bidirectional"))
      (node (ref "U$25") (pin "7") (pinfunction "D_7") (pintype "bidirectional"))
      (node (ref "U$26") (pin "7") (pinfunction "D_7") (pintype "bidirectional"))
    )
    (net (code "105") (name "Net-(HT16K5-ROW4{slash}K2)") (class "Default")
      (node (ref "HT16K5") (pin "P$21") (pinfunction "ROW4/K2_P$21") (pintype "bidirectional"))
      (node (ref "U$23") (pin "1") (pinfunction "E_1") (pintype "bidirectional"))
      (node (ref "U$24") (pin "1") (pinfunction "E_1") (pintype "bidirectional"))
      (node (ref "U$25") (pin "1") (pinfunction "E_1") (pintype "bidirectional"))
      (node (ref "U$26") (pin "1") (pinfunction "E_1") (pintype "bidirectional"))
    )
    (net (code "106") (name "Net-(HT16K5-ROW5{slash}K3)") (class "Default")
      (node (ref "HT16K5") (pin "P$20") (pinfunction "ROW5/K3_P$20") (pintype "bidirectional"))
      (node (ref "U$23") (pin "18") (pinfunction "F_18") (pintype "bidirectional"))
      (node (ref "U$24") (pin "18") (pinfunction "F_18") (pintype "bidirectional"))
      (node (ref "U$25") (pin "18") (pinfunction "F_18") (pintype "bidirectional"))
      (node (ref "U$26") (pin "18") (pinfunction "F_18") (pintype "bidirectional"))
    )
    (net (code "107") (name "Net-(HT16K5-ROW6{slash}K4)") (class "Default")
      (node (ref "HT16K5") (pin "P$19") (pinfunction "ROW6/K4_P$19") (pintype "bidirectional"))
      (node (ref "U$23") (pin "13") (pinfunction "N_13") (pintype "bidirectional"))
      (node (ref "U$24") (pin "13") (pinfunction "N_13") (pintype "bidirectional"))
      (node (ref "U$25") (pin "13") (pinfunction "N_13") (pintype "bidirectional"))
      (node (ref "U$26") (pin "13") (pinfunction "N_13") (pintype "bidirectional"))
    )
    (net (code "108") (name "Net-(HT16K5-ROW7{slash}K5)") (class "Default")
      (node (ref "HT16K5") (pin "P$18") (pinfunction "ROW7/K5_P$18") (pintype "bidirectional"))
      (node (ref "U$23") (pin "6") (pinfunction "J_6") (pintype "bidirectional"))
      (node (ref "U$24") (pin "6") (pinfunction "J_6") (pintype "bidirectional"))
      (node (ref "U$25") (pin "6") (pinfunction "J_6") (pintype "bidirectional"))
      (node (ref "U$26") (pin "6") (pinfunction "J_6") (pintype "bidirectional"))
    )
    (net (code "109") (name "Net-(HT16K5-ROW8{slash}K6)") (class "Default")
      (node (ref "HT16K5") (pin "P$17") (pinfunction "ROW8/K6_P$17") (pintype "bidirectional"))
      (node (ref "U$23") (pin "17") (pinfunction "P_17") (pintype "bidirectional"))
      (node (ref "U$24") (pin "17") (pinfunction "P_17") (pintype "bidirectional"))
      (node (ref "U$25") (pin "17") (pinfunction "P_17") (pintype "bidirectional"))
      (node (ref "U$26") (pin "17") (pinfunction "P_17") (pintype "bidirectional"))
    )
    (net (code "110") (name "Net-(HT16K5-ROW9{slash}K7)") (class "Default")
      (node (ref "HT16K5") (pin "P$16") (pinfunction "ROW9/K7_P$16") (pintype "bidirectional"))
      (node (ref "U$23") (pin "15") (pinfunction "G_15") (pintype "bidirectional"))
      (node (ref "U$24") (pin "15") (pinfunction "G_15") (pintype "bidirectional"))
      (node (ref "U$25") (pin "15") (pinfunction "G_15") (pintype "bidirectional"))
      (node (ref "U$26") (pin "15") (pinfunction "G_15") (pintype "bidirectional"))
    )
    (net (code "111") (name "Net-(HT16K5-ROW10{slash}K8)") (class "Default")
      (node (ref "HT16K5") (pin "P$15") (pinfunction "ROW10/K8_P$15") (pintype "bidirectional"))
      (node (ref "U$23") (pin "14") (pinfunction "H_14") (pintype "bidirectional"))
      (node (ref "U$24") (pin "14") (pinfunction "H_14") (pintype "bidirectional"))
      (node (ref "U$25") (pin "14") (pinfunction "H_14") (pintype "bidirectional"))
      (node (ref "U$26") (pin "14") (pinfunction "H_14") (pintype "bidirectional"))
    )
    (net (code "112") (name "Net-(HT16K5-ROW11{slash}K9)") (class "Default")
      (node (ref "HT16K5") (pin "P$14") (pinfunction "ROW11/K9_P$14") (pintype "bidirectional"))
      (node (ref "U$23") (pin "2") (pinfunction "M_2") (pintype "bidirectional"))
      (node (ref "U$24") (pin "2") (pinfunction "M_2") (pintype "bidirectional"))
      (node (ref "U$25") (pin "2") (pinfunction "M_2") (pintype "bidirectional"))
      (node (ref "U$26") (pin "2") (pinfunction "M_2") (pintype "bidirectional"))
    )
    (net (code "113") (name "Net-(HT16K5-ROW12{slash}K10)") (class "Default")
      (node (ref "HT16K5") (pin "P$13") (pinfunction "ROW12/K10_P$13") (pintype "bidirectional"))
      (node (ref "U$23") (pin "4") (pinfunction "L_4") (pintype "bidirectional"))
      (node (ref "U$24") (pin "4") (pinfunction "L_4") (pintype "bidirectional"))
      (node (ref "U$25") (pin "4") (pinfunction "L_4") (pintype "bidirectional"))
      (node (ref "U$26") (pin "4") (pinfunction "L_4") (pintype "bidirectional"))
    )
    (net (code "114") (name "Net-(HT16K5-ROW13{slash}K11)") (class "Default")
      (node (ref "HT16K5") (pin "P$12") (pinfunction "ROW13/K11_P$12") (pintype "bidirectional"))
      (node (ref "U$23") (pin "5") (pinfunction "K_5") (pintype "bidirectional"))
      (node (ref "U$24") (pin "5") (pinfunction "K_5") (pintype "bidirectional"))
      (node (ref "U$25") (pin "5") (pinfunction "K_5") (pintype "bidirectional"))
      (node (ref "U$26") (pin "5") (pinfunction "K_5") (pintype "bidirectional"))
    )
    (net (code "115") (name "Net-(HT16K5-ROW14{slash}K12)") (class "Default")
      (node (ref "HT16K5") (pin "P$11") (pinfunction "ROW14/K12_P$11") (pintype "bidirectional"))
      (node (ref "U$23") (pin "8") (pinfunction "DP_8") (pintype "bidirectional"))
      (node (ref "U$24") (pin "8") (pinfunction "DP_8") (pintype "bidirectional"))
      (node (ref "U$25") (pin "8") (pinfunction "DP_8") (pintype "bidirectional"))
      (node (ref "U$26") (pin "8") (pinfunction "DP_8") (pintype "bidirectional"))
    )
    (net (code "116") (name "Net-(HT16K6-COM0{slash}AD)") (class "Default")
      (node (ref "D7") (pin "A") (pinfunction "A_A") (pintype "passive"))
      (node (ref "HT16K6") (pin "P$2") (pinfunction "COM0/AD_P$2") (pintype "bidirectional"))
      (node (ref "U$27") (pin "16") (pinfunction "COM1_16") (pintype "bidirectional"))
    )
    (net (code "117") (name "Net-(HT16K6-COM1{slash}KS0)") (class "Default")
      (node (ref "HT16K6") (pin "P$3") (pinfunction "COM1/KS0_P$3") (pintype "bidirectional"))
      (node (ref "U$27") (pin "11") (pinfunction "COM2_11") (pintype "bidirectional"))
    )
    (net (code "118") (name "Net-(HT16K6-COM2{slash}KS1)") (class "Default")
      (node (ref "HT16K6") (pin "P$4") (pinfunction "COM2/KS1_P$4") (pintype "bidirectional"))
      (node (ref "U$28") (pin "16") (pinfunction "COM1_16") (pintype "bidirectional"))
    )
    (net (code "119") (name "Net-(HT16K6-COM3{slash}KS2)") (class "Default")
      (node (ref "HT16K6") (pin "P$5") (pinfunction "COM3/KS2_P$5") (pintype "bidirectional"))
      (node (ref "U$28") (pin "11") (pinfunction "COM2_11") (pintype "bidirectional"))
    )
    (net (code "120") (name "Net-(HT16K6-COM4)") (class "Default")
      (node (ref "HT16K6") (pin "P$6") (pinfunction "COM4_P$6") (pintype "bidirectional"))
      (node (ref "U$29") (pin "16") (pinfunction "COM1_16") (pintype "bidirectional"))
    )
    (net (code "121") (name "Net-(HT16K6-COM5)") (class "Default")
      (node (ref "HT16K6") (pin "P$7") (pinfunction "COM5_P$7") (pintype "bidirectional"))
      (node (ref "U$29") (pin "11") (pinfunction "COM2_11") (pintype "bidirectional"))
    )
    (net (code "122") (name "Net-(HT16K6-COM6)") (class "Default")
      (node (ref "HT16K6") (pin "P$8") (pinfunction "COM6_P$8") (pintype "bidirectional"))
      (node (ref "U$30") (pin "16") (pinfunction "COM1_16") (pintype "bidirectional"))
    )
    (net (code "123") (name "Net-(HT16K6-COM7)") (class "Default")
      (node (ref "HT16K6") (pin "P$9") (pinfunction "COM7_P$9") (pintype "bidirectional"))
      (node (ref "U$30") (pin "11") (pinfunction "COM2_11") (pintype "bidirectional"))
    )
    (net (code "124") (name "Net-(HT16K6-ROW3{slash}K1)") (class "Default")
      (node (ref "HT16K6") (pin "P$22") (pinfunction "ROW3/K1_P$22") (pintype "bidirectional"))
      (node (ref "U$27") (pin "7") (pinfunction "D_7") (pintype "bidirectional"))
      (node (ref "U$28") (pin "7") (pinfunction "D_7") (pintype "bidirectional"))
      (node (ref "U$29") (pin "7") (pinfunction "D_7") (pintype "bidirectional"))
      (node (ref "U$30") (pin "7") (pinfunction "D_7") (pintype "bidirectional"))
    )
    (net (code "125") (name "Net-(HT16K6-ROW4{slash}K2)") (class "Default")
      (node (ref "HT16K6") (pin "P$21") (pinfunction "ROW4/K2_P$21") (pintype "bidirectional"))
      (node (ref "U$27") (pin "1") (pinfunction "E_1") (pintype "bidirectional"))
      (node (ref "U$28") (pin "1") (pinfunction "E_1") (pintype "bidirectional"))
      (node (ref "U$29") (pin "1") (pinfunction "E_1") (pintype "bidirectional"))
      (node (ref "U$30") (pin "1") (pinfunction "E_1") (pintype "bidirectional"))
    )
    (net (code "126") (name "Net-(HT16K6-ROW5{slash}K3)") (class "Default")
      (node (ref "HT16K6") (pin "P$20") (pinfunction "ROW5/K3_P$20") (pintype "bidirectional"))
      (node (ref "U$27") (pin "18") (pinfunction "F_18") (pintype "bidirectional"))
      (node (ref "U$28") (pin "18") (pinfunction "F_18") (pintype "bidirectional"))
      (node (ref "U$29") (pin "18") (pinfunction "F_18") (pintype "bidirectional"))
      (node (ref "U$30") (pin "18") (pinfunction "F_18") (pintype "bidirectional"))
    )
    (net (code "127") (name "Net-(HT16K6-ROW6{slash}K4)") (class "Default")
      (node (ref "HT16K6") (pin "P$19") (pinfunction "ROW6/K4_P$19") (pintype "bidirectional"))
      (node (ref "U$27") (pin "13") (pinfunction "N_13") (pintype "bidirectional"))
      (node (ref "U$28") (pin "13") (pinfunction "N_13") (pintype "bidirectional"))
      (node (ref "U$29") (pin "13") (pinfunction "N_13") (pintype "bidirectional"))
      (node (ref "U$30") (pin "13") (pinfunction "N_13") (pintype "bidirectional"))
    )
    (net (code "128") (name "Net-(HT16K6-ROW7{slash}K5)") (class "Default")
      (node (ref "HT16K6") (pin "P$18") (pinfunction "ROW7/K5_P$18") (pintype "bidirectional"))
      (node (ref "U$27") (pin "6") (pinfunction "J_6") (pintype "bidirectional"))
      (node (ref "U$28") (pin "6") (pinfunction "J_6") (pintype "bidirectional"))
      (node (ref "U$29") (pin "6") (pinfunction "J_6") (pintype "bidirectional"))
      (node (ref "U$30") (pin "6") (pinfunction "J_6") (pintype "bidirectional"))
    )
    (net (code "129") (name "Net-(HT16K6-ROW8{slash}K6)") (class "Default")
      (node (ref "HT16K6") (pin "P$17") (pinfunction "ROW8/K6_P$17") (pintype "bidirectional"))
      (node (ref "U$27") (pin "17") (pinfunction "P_17") (pintype "bidirectional"))
      (node (ref "U$28") (pin "17") (pinfunction "P_17") (pintype "bidirectional"))
      (node (ref "U$29") (pin "17") (pinfunction "P_17") (pintype "bidirectional"))
      (node (ref "U$30") (pin "17") (pinfunction "P_17") (pintype "bidirectional"))
    )
    (net (code "130") (name "Net-(HT16K6-ROW9{slash}K7)") (class "Default")
      (node (ref "HT16K6") (pin "P$16") (pinfunction "ROW9/K7_P$16") (pintype "bidirectional"))
      (node (ref "U$27") (pin "15") (pinfunction "G_15") (pintype "bidirectional"))
      (node (ref "U$28") (pin "15") (pinfunction "G_15") (pintype "bidirectional"))
      (node (ref "U$29") (pin "15") (pinfunction "G_15") (pintype "bidirectional"))
      (node (ref "U$30") (pin "15") (pinfunction "G_15") (pintype "bidirectional"))
    )
    (net (code "131") (name "Net-(HT16K6-ROW10{slash}K8)") (class "Default")
      (node (ref "HT16K6") (pin "P$15") (pinfunction "ROW10/K8_P$15") (pintype "bidirectional"))
      (node (ref "U$27") (pin "14") (pinfunction "H_14") (pintype "bidirectional"))
      (node (ref "U$28") (pin "14") (pinfunction "H_14") (pintype "bidirectional"))
      (node (ref "U$29") (pin "14") (pinfunction "H_14") (pintype "bidirectional"))
      (node (ref "U$30") (pin "14") (pinfunction "H_14") (pintype "bidirectional"))
    )
    (net (code "132") (name "Net-(HT16K6-ROW11{slash}K9)") (class "Default")
      (node (ref "HT16K6") (pin "P$14") (pinfunction "ROW11/K9_P$14") (pintype "bidirectional"))
      (node (ref "U$27") (pin "2") (pinfunction "M_2") (pintype "bidirectional"))
      (node (ref "U$28") (pin "2") (pinfunction "M_2") (pintype "bidirectional"))
      (node (ref "U$29") (pin "2") (pinfunction "M_2") (pintype "bidirectional"))
      (node (ref "U$30") (pin "2") (pinfunction "M_2") (pintype "bidirectional"))
    )
    (net (code "133") (name "Net-(HT16K6-ROW12{slash}K10)") (class "Default")
      (node (ref "HT16K6") (pin "P$13") (pinfunction "ROW12/K10_P$13") (pintype "bidirectional"))
      (node (ref "U$27") (pin "4") (pinfunction "L_4") (pintype "bidirectional"))
      (node (ref "U$28") (pin "4") (pinfunction "L_4") (pintype "bidirectional"))
      (node (ref "U$29") (pin "4") (pinfunction "L_4") (pintype "bidirectional"))
      (node (ref "U$30") (pin "4") (pinfunction "L_4") (pintype "bidirectional"))
    )
    (net (code "134") (name "Net-(HT16K6-ROW13{slash}K11)") (class "Default")
      (node (ref "HT16K6") (pin "P$12") (pinfunction "ROW13/K11_P$12") (pintype "bidirectional"))
      (node (ref "U$27") (pin "5") (pinfunction "K_5") (pintype "bidirectional"))
      (node (ref "U$28") (pin "5") (pinfunction "K_5") (pintype "bidirectional"))
      (node (ref "U$29") (pin "5") (pinfunction "K_5") (pintype "bidirectional"))
      (node (ref "U$30") (pin "5") (pinfunction "K_5") (pintype "bidirectional"))
    )
    (net (code "135") (name "Net-(HT16K6-ROW14{slash}K12)") (class "Default")
      (node (ref "HT16K6") (pin "P$11") (pinfunction "ROW14/K12_P$11") (pintype "bidirectional"))
      (node (ref "U$27") (pin "8") (pinfunction "DP_8") (pintype "bidirectional"))
      (node (ref "U$28") (pin "8") (pinfunction "DP_8") (pintype "bidirectional"))
      (node (ref "U$29") (pin "8") (pinfunction "DP_8") (pintype "bidirectional"))
      (node (ref "U$30") (pin "8") (pinfunction "DP_8") (pintype "bidirectional"))
    )
    (net (code "136") (name "Net-(HT16K7-COM0{slash}AD)") (class "Default")
      (node (ref "D8") (pin "A") (pinfunction "A_A") (pintype "passive"))
      (node (ref "HT16K7") (pin "P$2") (pinfunction "COM0/AD_P$2") (pintype "bidirectional"))
      (node (ref "U$31") (pin "16") (pinfunction "COM1_16") (pintype "bidirectional"))
    )
    (net (code "137") (name "Net-(HT16K7-COM1{slash}KS0)") (class "Default")
      (node (ref "HT16K7") (pin "P$3") (pinfunction "COM1/KS0_P$3") (pintype "bidirectional"))
      (node (ref "U$31") (pin "11") (pinfunction "COM2_11") (pintype "bidirectional"))
    )
    (net (code "138") (name "Net-(HT16K7-COM2{slash}KS1)") (class "Default")
      (node (ref "HT16K7") (pin "P$4") (pinfunction "COM2/KS1_P$4") (pintype "bidirectional"))
      (node (ref "U$32") (pin "16") (pinfunction "COM1_16") (pintype "bidirectional"))
    )
    (net (code "139") (name "Net-(HT16K7-COM3{slash}KS2)") (class "Default")
      (node (ref "HT16K7") (pin "P$5") (pinfunction "COM3/KS2_P$5") (pintype "bidirectional"))
      (node (ref "U$32") (pin "11") (pinfunction "COM2_11") (pintype "bidirectional"))
    )
    (net (code "140") (name "Net-(HT16K7-COM4)") (class "Default")
      (node (ref "HT16K7") (pin "P$6") (pinfunction "COM4_P$6") (pintype "bidirectional"))
      (node (ref "U$33") (pin "16") (pinfunction "COM1_16") (pintype "bidirectional"))
    )
    (net (code "141") (name "Net-(HT16K7-COM5)") (class "Default")
      (node (ref "HT16K7") (pin "P$7") (pinfunction "COM5_P$7") (pintype "bidirectional"))
      (node (ref "U$33") (pin "11") (pinfunction "COM2_11") (pintype "bidirectional"))
    )
    (net (code "142") (name "Net-(HT16K7-COM6)") (class "Default")
      (node (ref "HT16K7") (pin "P$8") (pinfunction "COM6_P$8") (pintype "bidirectional"))
      (node (ref "U$34") (pin "16") (pinfunction "COM1_16") (pintype "bidirectional"))
    )
    (net (code "143") (name "Net-(HT16K7-COM7)") (class "Default")
      (node (ref "HT16K7") (pin "P$9") (pinfunction "COM7_P$9") (pintype "bidirectional"))
      (node (ref "U$34") (pin "11") (pinfunction "COM2_11") (pintype "bidirectional"))
    )
    (net (code "144") (name "Net-(HT16K7-ROW3{slash}K1)") (class "Default")
      (node (ref "HT16K7") (pin "P$22") (pinfunction "ROW3/K1_P$22") (pintype "bidirectional"))
      (node (ref "U$31") (pin "7") (pinfunction "D_7") (pintype "bidirectional"))
      (node (ref "U$32") (pin "7") (pinfunction "D_7") (pintype "bidirectional"))
      (node (ref "U$33") (pin "7") (pinfunction "D_7") (pintype "bidirectional"))
      (node (ref "U$34") (pin "7") (pinfunction "D_7") (pintype "bidirectional"))
    )
    (net (code "145") (name "Net-(HT16K7-ROW4{slash}K2)") (class "Default")
      (node (ref "HT16K7") (pin "P$21") (pinfunction "ROW4/K2_P$21") (pintype "bidirectional"))
      (node (ref "U$31") (pin "1") (pinfunction "E_1") (pintype "bidirectional"))
      (node (ref "U$32") (pin "1") (pinfunction "E_1") (pintype "bidirectional"))
      (node (ref "U$33") (pin "1") (pinfunction "E_1") (pintype "bidirectional"))
      (node (ref "U$34") (pin "1") (pinfunction "E_1") (pintype "bidirectional"))
    )
    (net (code "146") (name "Net-(HT16K7-ROW5{slash}K3)") (class "Default")
      (node (ref "HT16K7") (pin "P$20") (pinfunction "ROW5/K3_P$20") (pintype "bidirectional"))
      (node (ref "U$31") (pin "18") (pinfunction "F_18") (pintype "bidirectional"))
      (node (ref "U$32") (pin "18") (pinfunction "F_18") (pintype "bidirectional"))
      (node (ref "U$33") (pin "18") (pinfunction "F_18") (pintype "bidirectional"))
      (node (ref "U$34") (pin "18") (pinfunction "F_18") (pintype "bidirectional"))
    )
    (net (code "147") (name "Net-(HT16K7-ROW6{slash}K4)") (class "Default")
      (node (ref "HT16K7") (pin "P$19") (pinfunction "ROW6/K4_P$19") (pintype "bidirectional"))
      (node (ref "U$31") (pin "13") (pinfunction "N_13") (pintype "bidirectional"))
      (node (ref "U$32") (pin "13") (pinfunction "N_13") (pintype "bidirectional"))
      (node (ref "U$33") (pin "13") (pinfunction "N_13") (pintype "bidirectional"))
      (node (ref "U$34") (pin "13") (pinfunction "N_13") (pintype "bidirectional"))
    )
    (net (code "148") (name "Net-(HT16K7-ROW7{slash}K5)") (class "Default")
      (node (ref "HT16K7") (pin "P$18") (pinfunction "ROW7/K5_P$18") (pintype "bidirectional"))
      (node (ref "U$31") (pin "6") (pinfunction "J_6") (pintype "bidirectional"))
      (node (ref "U$32") (pin "6") (pinfunction "J_6") (pintype "bidirectional"))
      (node (ref "U$33") (pin "6") (pinfunction "J_6") (pintype "bidirectional"))
      (node (ref "U$34") (pin "6") (pinfunction "J_6") (pintype "bidirectional"))
    )
    (net (code "149") (name "Net-(HT16K7-ROW8{slash}K6)") (class "Default")
      (node (ref "HT16K7") (pin "P$17") (pinfunction "ROW8/K6_P$17") (pintype "bidirectional"))
      (node (ref "U$31") (pin "17") (pinfunction "P_17") (pintype "bidirectional"))
      (node (ref "U$32") (pin "17") (pinfunction "P_17") (pintype "bidirectional"))
      (node (ref "U$33") (pin "17") (pinfunction "P_17") (pintype "bidirectional"))
      (node (ref "U$34") (pin "17") (pinfunction "P_17") (pintype "bidirectional"))
    )
    (net (code "150") (name "Net-(HT16K7-ROW9{slash}K7)") (class "Default")
      (node (ref "HT16K7") (pin "P$16") (pinfunction "ROW9/K7_P$16") (pintype "bidirectional"))
      (node (ref "U$31") (pin "15") (pinfunction "G_15") (pintype "bidirectional"))
      (node (ref "U$32") (pin "15") (pinfunction "G_15") (pintype "bidirectional"))
      (node (ref "U$33") (pin "15") (pinfunction "G_15") (pintype "bidirectional"))
      (node (ref "U$34") (pin "15") (pinfunction "G_15") (pintype "bidirectional"))
    )
    (net (code "151") (name "Net-(HT16K7-ROW10{slash}K8)") (class "Default")
      (node (ref "HT16K7") (pin "P$15") (pinfunction "ROW10/K8_P$15") (pintype "bidirectional"))
      (node (ref "U$31") (pin "14") (pinfunction "H_14") (pintype "bidirectional"))
      (node (ref "U$32") (pin "14") (pinfunction "H_14") (pintype "bidirectional"))
      (node (ref "U$33") (pin "14") (pinfunction "H_14") (pintype "bidirectional"))
      (node (ref "U$34") (pin "14") (pinfunction "H_14") (pintype "bidirectional"))
    )
    (net (code "152") (name "Net-(HT16K7-ROW11{slash}K9)") (class "Default")
      (node (ref "HT16K7") (pin "P$14") (pinfunction "ROW11/K9_P$14") (pintype "bidirectional"))
      (node (ref "U$31") (pin "2") (pinfunction "M_2") (pintype "bidirectional"))
      (node (ref "U$32") (pin "2") (pinfunction "M_2") (pintype "bidirectional"))
      (node (ref "U$33") (pin "2") (pinfunction "M_2") (pintype "bidirectional"))
      (node (ref "U$34") (pin "2") (pinfunction "M_2") (pintype "bidirectional"))
    )
    (net (code "153") (name "Net-(HT16K7-ROW12{slash}K10)") (class "Default")
      (node (ref "HT16K7") (pin "P$13") (pinfunction "ROW12/K10_P$13") (pintype "bidirectional"))
      (node (ref "U$31") (pin "4") (pinfunction "L_4") (pintype "bidirectional"))
      (node (ref "U$32") (pin "4") (pinfunction "L_4") (pintype "bidirectional"))
      (node (ref "U$33") (pin "4") (pinfunction "L_4") (pintype "bidirectional"))
      (node (ref "U$34") (pin "4") (pinfunction "L_4") (pintype "bidirectional"))
    )
    (net (code "154") (name "Net-(HT16K7-ROW13{slash}K11)") (class "Default")
      (node (ref "HT16K7") (pin "P$12") (pinfunction "ROW13/K11_P$12") (pintype "bidirectional"))
      (node (ref "U$31") (pin "5") (pinfunction "K_5") (pintype "bidirectional"))
      (node (ref "U$32") (pin "5") (pinfunction "K_5") (pintype "bidirectional"))
      (node (ref "U$33") (pin "5") (pinfunction "K_5") (pintype "bidirectional"))
      (node (ref "U$34") (pin "5") (pinfunction "K_5") (pintype "bidirectional"))
    )
    (net (code "155") (name "Net-(HT16K7-ROW14{slash}K12)") (class "Default")
      (node (ref "HT16K7") (pin "P$11") (pinfunction "ROW14/K12_P$11") (pintype "bidirectional"))
      (node (ref "U$31") (pin "8") (pinfunction "DP_8") (pintype "bidirectional"))
      (node (ref "U$32") (pin "8") (pinfunction "DP_8") (pintype "bidirectional"))
      (node (ref "U$33") (pin "8") (pinfunction "DP_8") (pintype "bidirectional"))
      (node (ref "U$34") (pin "8") (pinfunction "DP_8") (pintype "bidirectional"))
    )
    (net (code "156") (name "Net-(HT16K8-COM0{slash}AD)") (class "Default")
      (node (ref "D9") (pin "A") (pinfunction "A_A") (pintype "passive"))
      (node (ref "HT16K8") (pin "P$2") (pinfunction "COM0/AD_P$2") (pintype "bidirectional"))
      (node (ref "U$37") (pin "16") (pinfunction "COM1_16") (pintype "bidirectional"))
    )
    (net (code "157") (name "Net-(HT16K8-COM1{slash}KS0)") (class "Default")
      (node (ref "HT16K8") (pin "P$3") (pinfunction "COM1/KS0_P$3") (pintype "bidirectional"))
      (node (ref "U$37") (pin "11") (pinfunction "COM2_11") (pintype "bidirectional"))
    )
    (net (code "158") (name "Net-(HT16K8-COM2{slash}KS1)") (class "Default")
      (node (ref "HT16K8") (pin "P$4") (pinfunction "COM2/KS1_P$4") (pintype "bidirectional"))
      (node (ref "U$38") (pin "16") (pinfunction "COM1_16") (pintype "bidirectional"))
    )
    (net (code "159") (name "Net-(HT16K8-COM3{slash}KS2)") (class "Default")
      (node (ref "HT16K8") (pin "P$5") (pinfunction "COM3/KS2_P$5") (pintype "bidirectional"))
      (node (ref "U$38") (pin "11") (pinfunction "COM2_11") (pintype "bidirectional"))
    )
    (net (code "160") (name "Net-(HT16K8-COM4)") (class "Default")
      (node (ref "HT16K8") (pin "P$6") (pinfunction "COM4_P$6") (pintype "bidirectional"))
      (node (ref "U$39") (pin "16") (pinfunction "COM1_16") (pintype "bidirectional"))
    )
    (net (code "161") (name "Net-(HT16K8-COM5)") (class "Default")
      (node (ref "HT16K8") (pin "P$7") (pinfunction "COM5_P$7") (pintype "bidirectional"))
      (node (ref "U$39") (pin "11") (pinfunction "COM2_11") (pintype "bidirectional"))
    )
    (net (code "162") (name "Net-(HT16K8-COM6)") (class "Default")
      (node (ref "HT16K8") (pin "P$8") (pinfunction "COM6_P$8") (pintype "bidirectional"))
      (node (ref "U$40") (pin "16") (pinfunction "COM1_16") (pintype "bidirectional"))
    )
    (net (code "163") (name "Net-(HT16K8-COM7)") (class "Default")
      (node (ref "HT16K8") (pin "P$9") (pinfunction "COM7_P$9") (pintype "bidirectional"))
      (node (ref "U$40") (pin "11") (pinfunction "COM2_11") (pintype "bidirectional"))
    )
    (net (code "164") (name "Net-(HT16K8-ROW3{slash}K1)") (class "Default")
      (node (ref "HT16K8") (pin "P$22") (pinfunction "ROW3/K1_P$22") (pintype "bidirectional"))
      (node (ref "U$37") (pin "7") (pinfunction "D_7") (pintype "bidirectional"))
      (node (ref "U$38") (pin "7") (pinfunction "D_7") (pintype "bidirectional"))
      (node (ref "U$39") (pin "7") (pinfunction "D_7") (pintype "bidirectional"))
      (node (ref "U$40") (pin "7") (pinfunction "D_7") (pintype "bidirectional"))
    )
    (net (code "165") (name "Net-(HT16K8-ROW4{slash}K2)") (class "Default")
      (node (ref "HT16K8") (pin "P$21") (pinfunction "ROW4/K2_P$21") (pintype "bidirectional"))
      (node (ref "U$37") (pin "1") (pinfunction "E_1") (pintype "bidirectional"))
      (node (ref "U$38") (pin "1") (pinfunction "E_1") (pintype "bidirectional"))
      (node (ref "U$39") (pin "1") (pinfunction "E_1") (pintype "bidirectional"))
      (node (ref "U$40") (pin "1") (pinfunction "E_1") (pintype "bidirectional"))
    )
    (net (code "166") (name "Net-(HT16K8-ROW5{slash}K3)") (class "Default")
      (node (ref "HT16K8") (pin "P$20") (pinfunction "ROW5/K3_P$20") (pintype "bidirectional"))
      (node (ref "U$37") (pin "18") (pinfunction "F_18") (pintype "bidirectional"))
      (node (ref "U$38") (pin "18") (pinfunction "F_18") (pintype "bidirectional"))
      (node (ref "U$39") (pin "18") (pinfunction "F_18") (pintype "bidirectional"))
      (node (ref "U$40") (pin "18") (pinfunction "F_18") (pintype "bidirectional"))
    )
    (net (code "167") (name "Net-(HT16K8-ROW6{slash}K4)") (class "Default")
      (node (ref "HT16K8") (pin "P$19") (pinfunction "ROW6/K4_P$19") (pintype "bidirectional"))
      (node (ref "U$37") (pin "13") (pinfunction "N_13") (pintype "bidirectional"))
      (node (ref "U$38") (pin "13") (pinfunction "N_13") (pintype "bidirectional"))
      (node (ref "U$39") (pin "13") (pinfunction "N_13") (pintype "bidirectional"))
      (node (ref "U$40") (pin "13") (pinfunction "N_13") (pintype "bidirectional"))
    )
    (net (code "168") (name "Net-(HT16K8-ROW7{slash}K5)") (class "Default")
      (node (ref "HT16K8") (pin "P$18") (pinfunction "ROW7/K5_P$18") (pintype "bidirectional"))
      (node (ref "U$37") (pin "6") (pinfunction "J_6") (pintype "bidirectional"))
      (node (ref "U$38") (pin "6") (pinfunction "J_6") (pintype "bidirectional"))
      (node (ref "U$39") (pin "6") (pinfunction "J_6") (pintype "bidirectional"))
      (node (ref "U$40") (pin "6") (pinfunction "J_6") (pintype "bidirectional"))
    )
    (net (code "169") (name "Net-(HT16K8-ROW8{slash}K6)") (class "Default")
      (node (ref "HT16K8") (pin "P$17") (pinfunction "ROW8/K6_P$17") (pintype "bidirectional"))
      (node (ref "U$37") (pin "17") (pinfunction "P_17") (pintype "bidirectional"))
      (node (ref "U$38") (pin "17") (pinfunction "P_17") (pintype "bidirectional"))
      (node (ref "U$39") (pin "17") (pinfunction "P_17") (pintype "bidirectional"))
      (node (ref "U$40") (pin "17") (pinfunction "P_17") (pintype "bidirectional"))
    )
    (net (code "170") (name "Net-(HT16K8-ROW9{slash}K7)") (class "Default")
      (node (ref "HT16K8") (pin "P$16") (pinfunction "ROW9/K7_P$16") (pintype "bidirectional"))
      (node (ref "U$37") (pin "15") (pinfunction "G_15") (pintype "bidirectional"))
      (node (ref "U$38") (pin "15") (pinfunction "G_15") (pintype "bidirectional"))
      (node (ref "U$39") (pin "15") (pinfunction "G_15") (pintype "bidirectional"))
      (node (ref "U$40") (pin "15") (pinfunction "G_15") (pintype "bidirectional"))
    )
    (net (code "171") (name "Net-(HT16K8-ROW10{slash}K8)") (class "Default")
      (node (ref "HT16K8") (pin "P$15") (pinfunction "ROW10/K8_P$15") (pintype "bidirectional"))
      (node (ref "U$37") (pin "14") (pinfunction "H_14") (pintype "bidirectional"))
      (node (ref "U$38") (pin "14") (pinfunction "H_14") (pintype "bidirectional"))
      (node (ref "U$39") (pin "14") (pinfunction "H_14") (pintype "bidirectional"))
      (node (ref "U$40") (pin "14") (pinfunction "H_14") (pintype "bidirectional"))
    )
    (net (code "172") (name "Net-(HT16K8-ROW11{slash}K9)") (class "Default")
      (node (ref "HT16K8") (pin "P$14") (pinfunction "ROW11/K9_P$14") (pintype "bidirectional"))
      (node (ref "U$37") (pin "2") (pinfunction "M_2") (pintype "bidirectional"))
      (node (ref "U$38") (pin "2") (pinfunction "M_2") (pintype "bidirectional"))
      (node (ref "U$39") (pin "2") (pinfunction "M_2") (pintype "bidirectional"))
      (node (ref "U$40") (pin "2") (pinfunction "M_2") (pintype "bidirectional"))
    )
    (net (code "173") (name "Net-(HT16K8-ROW12{slash}K10)") (class "Default")
      (node (ref "HT16K8") (pin "P$13") (pinfunction "ROW12/K10_P$13") (pintype "bidirectional"))
      (node (ref "U$37") (pin "4") (pinfunction "L_4") (pintype "bidirectional"))
      (node (ref "U$38") (pin "4") (pinfunction "L_4") (pintype "bidirectional"))
      (node (ref "U$39") (pin "4") (pinfunction "L_4") (pintype "bidirectional"))
      (node (ref "U$40") (pin "4") (pinfunction "L_4") (pintype "bidirectional"))
    )
    (net (code "174") (name "Net-(HT16K8-ROW13{slash}K11)") (class "Default")
      (node (ref "HT16K8") (pin "P$12") (pinfunction "ROW13/K11_P$12") (pintype "bidirectional"))
      (node (ref "U$37") (pin "5") (pinfunction "K_5") (pintype "bidirectional"))
      (node (ref "U$38") (pin "5") (pinfunction "K_5") (pintype "bidirectional"))
      (node (ref "U$39") (pin "5") (pinfunction "K_5") (pintype "bidirectional"))
      (node (ref "U$40") (pin "5") (pinfunction "K_5") (pintype "bidirectional"))
    )
    (net (code "175") (name "Net-(HT16K8-ROW14{slash}K12)") (class "Default")
      (node (ref "HT16K8") (pin "P$11") (pinfunction "ROW14/K12_P$11") (pintype "bidirectional"))
      (node (ref "U$37") (pin "8") (pinfunction "DP_8") (pintype "bidirectional"))
      (node (ref "U$38") (pin "8") (pinfunction "DP_8") (pintype "bidirectional"))
      (node (ref "U$39") (pin "8") (pinfunction "DP_8") (pintype "bidirectional"))
      (node (ref "U$40") (pin "8") (pinfunction "DP_8") (pintype "bidirectional"))
    )
    (net (code "176") (name "Net-(HT16K33-COM0{slash}AD)") (class "Default")
      (node (ref "D1") (pin "A") (pinfunction "A_A") (pintype "passive"))
      (node (ref "HT16K33") (pin "P$2") (pinfunction "COM0/AD_P$2") (pintype "bidirectional"))
      (node (ref "U$2") (pin "16") (pinfunction "COM1_16") (pintype "bidirectional"))
    )
    (net (code "177") (name "Net-(HT16K33-COM1{slash}KS0)") (class "Default")
      (node (ref "HT16K33") (pin "P$3") (pinfunction "COM1/KS0_P$3") (pintype "bidirectional"))
      (node (ref "U$2") (pin "11") (pinfunction "COM2_11") (pintype "bidirectional"))
    )
    (net (code "178") (name "Net-(HT16K33-COM2{slash}KS1)") (class "Default")
      (node (ref "HT16K33") (pin "P$4") (pinfunction "COM2/KS1_P$4") (pintype "bidirectional"))
      (node (ref "U$3") (pin "16") (pinfunction "COM1_16") (pintype "bidirectional"))
    )
    (net (code "179") (name "Net-(HT16K33-COM3{slash}KS2)") (class "Default")
      (node (ref "HT16K33") (pin "P$5") (pinfunction "COM3/KS2_P$5") (pintype "bidirectional"))
      (node (ref "U$3") (pin "11") (pinfunction "COM2_11") (pintype "bidirectional"))
    )
    (net (code "180") (name "Net-(HT16K33-COM4)") (class "Default")
      (node (ref "HT16K33") (pin "P$6") (pinfunction "COM4_P$6") (pintype "bidirectional"))
      (node (ref "U$4") (pin "16") (pinfunction "COM1_16") (pintype "bidirectional"))
    )
    (net (code "181") (name "Net-(HT16K33-COM5)") (class "Default")
      (node (ref "HT16K33") (pin "P$7") (pinfunction "COM5_P$7") (pintype "bidirectional"))
      (node (ref "U$4") (pin "11") (pinfunction "COM2_11") (pintype "bidirectional"))
    )
    (net (code "182") (name "Net-(HT16K33-COM6)") (class "Default")
      (node (ref "HT16K33") (pin "P$8") (pinfunction "COM6_P$8") (pintype "bidirectional"))
      (node (ref "U$5") (pin "16") (pinfunction "COM1_16") (pintype "bidirectional"))
    )
    (net (code "183") (name "Net-(HT16K33-COM7)") (class "Default")
      (node (ref "HT16K33") (pin "P$9") (pinfunction "COM7_P$9") (pintype "bidirectional"))
      (node (ref "U$5") (pin "11") (pinfunction "COM2_11") (pintype "bidirectional"))
    )
    (net (code "184") (name "Net-(HT16K33-ROW3{slash}K1)") (class "Default")
      (node (ref "HT16K33") (pin "P$22") (pinfunction "ROW3/K1_P$22") (pintype "bidirectional"))
      (node (ref "U$2") (pin "7") (pinfunction "D_7") (pintype "bidirectional"))
      (node (ref "U$3") (pin "7") (pinfunction "D_7") (pintype "bidirectional"))
      (node (ref "U$4") (pin "7") (pinfunction "D_7") (pintype "bidirectional"))
      (node (ref "U$5") (pin "7") (pinfunction "D_7") (pintype "bidirectional"))
    )
    (net (code "185") (name "Net-(HT16K33-ROW4{slash}K2)") (class "Default")
      (node (ref "HT16K33") (pin "P$21") (pinfunction "ROW4/K2_P$21") (pintype "bidirectional"))
      (node (ref "U$2") (pin "1") (pinfunction "E_1") (pintype "bidirectional"))
      (node (ref "U$3") (pin "1") (pinfunction "E_1") (pintype "bidirectional"))
      (node (ref "U$4") (pin "1") (pinfunction "E_1") (pintype "bidirectional"))
      (node (ref "U$5") (pin "1") (pinfunction "E_1") (pintype "bidirectional"))
    )
    (net (code "186") (name "Net-(HT16K33-ROW5{slash}K3)") (class "Default")
      (node (ref "HT16K33") (pin "P$20") (pinfunction "ROW5/K3_P$20") (pintype "bidirectional"))
      (node (ref "U$2") (pin "18") (pinfunction "F_18") (pintype "bidirectional"))
      (node (ref "U$3") (pin "18") (pinfunction "F_18") (pintype "bidirectional"))
      (node (ref "U$4") (pin "18") (pinfunction "F_18") (pintype "bidirectional"))
      (node (ref "U$5") (pin "18") (pinfunction "F_18") (pintype "bidirectional"))
    )
    (net (code "187") (name "Net-(HT16K33-ROW6{slash}K4)") (class "Default")
      (node (ref "HT16K33") (pin "P$19") (pinfunction "ROW6/K4_P$19") (pintype "bidirectional"))
      (node (ref "U$2") (pin "13") (pinfunction "N_13") (pintype "bidirectional"))
      (node (ref "U$3") (pin "13") (pinfunction "N_13") (pintype "bidirectional"))
      (node (ref "U$4") (pin "13") (pinfunction "N_13") (pintype "bidirectional"))
      (node (ref "U$5") (pin "13") (pinfunction "N_13") (pintype "bidirectional"))
    )
    (net (code "188") (name "Net-(HT16K33-ROW7{slash}K5)") (class "Default")
      (node (ref "HT16K33") (pin "P$18") (pinfunction "ROW7/K5_P$18") (pintype "bidirectional"))
      (node (ref "U$2") (pin "6") (pinfunction "J_6") (pintype "bidirectional"))
      (node (ref "U$3") (pin "6") (pinfunction "J_6") (pintype "bidirectional"))
      (node (ref "U$4") (pin "6") (pinfunction "J_6") (pintype "bidirectional"))
      (node (ref "U$5") (pin "6") (pinfunction "J_6") (pintype "bidirectional"))
    )
    (net (code "189") (name "Net-(HT16K33-ROW8{slash}K6)") (class "Default")
      (node (ref "HT16K33") (pin "P$17") (pinfunction "ROW8/K6_P$17") (pintype "bidirectional"))
      (node (ref "U$2") (pin "17") (pinfunction "P_17") (pintype "bidirectional"))
      (node (ref "U$3") (pin "17") (pinfunction "P_17") (pintype "bidirectional"))
      (node (ref "U$4") (pin "17") (pinfunction "P_17") (pintype "bidirectional"))
      (node (ref "U$5") (pin "17") (pinfunction "P_17") (pintype "bidirectional"))
    )
    (net (code "190") (name "Net-(HT16K33-ROW9{slash}K7)") (class "Default")
      (node (ref "HT16K33") (pin "P$16") (pinfunction "ROW9/K7_P$16") (pintype "bidirectional"))
      (node (ref "U$2") (pin "15") (pinfunction "G_15") (pintype "bidirectional"))
      (node (ref "U$3") (pin "15") (pinfunction "G_15") (pintype "bidirectional"))
      (node (ref "U$4") (pin "15") (pinfunction "G_15") (pintype "bidirectional"))
      (node (ref "U$5") (pin "15") (pinfunction "G_15") (pintype "bidirectional"))
    )
    (net (code "191") (name "Net-(HT16K33-ROW10{slash}K8)") (class "Default")
      (node (ref "HT16K33") (pin "P$15") (pinfunction "ROW10/K8_P$15") (pintype "bidirectional"))
      (node (ref "U$2") (pin "14") (pinfunction "H_14") (pintype "bidirectional"))
      (node (ref "U$3") (pin "14") (pinfunction "H_14") (pintype "bidirectional"))
      (node (ref "U$4") (pin "14") (pinfunction "H_14") (pintype "bidirectional"))
      (node (ref "U$5") (pin "14") (pinfunction "H_14") (pintype "bidirectional"))
    )
    (net (code "192") (name "Net-(HT16K33-ROW11{slash}K9)") (class "Default")
      (node (ref "HT16K33") (pin "P$14") (pinfunction "ROW11/K9_P$14") (pintype "bidirectional"))
      (node (ref "U$2") (pin "2") (pinfunction "M_2") (pintype "bidirectional"))
      (node (ref "U$3") (pin "2") (pinfunction "M_2") (pintype "bidirectional"))
      (node (ref "U$4") (pin "2") (pinfunction "M_2") (pintype "bidirectional"))
      (node (ref "U$5") (pin "2") (pinfunction "M_2") (pintype "bidirectional"))
    )
    (net (code "193") (name "Net-(HT16K33-ROW12{slash}K10)") (class "Default")
      (node (ref "HT16K33") (pin "P$13") (pinfunction "ROW12/K10_P$13") (pintype "bidirectional"))
      (node (ref "U$2") (pin "4") (pinfunction "L_4") (pintype "bidirectional"))
      (node (ref "U$3") (pin "4") (pinfunction "L_4") (pintype "bidirectional"))
      (node (ref "U$4") (pin "4") (pinfunction "L_4") (pintype "bidirectional"))
      (node (ref "U$5") (pin "4") (pinfunction "L_4") (pintype "bidirectional"))
    )
    (net (code "194") (name "Net-(HT16K33-ROW13{slash}K11)") (class "Default")
      (node (ref "HT16K33") (pin "P$12") (pinfunction "ROW13/K11_P$12") (pintype "bidirectional"))
      (node (ref "U$2") (pin "5") (pinfunction "K_5") (pintype "bidirectional"))
      (node (ref "U$3") (pin "5") (pinfunction "K_5") (pintype "bidirectional"))
      (node (ref "U$4") (pin "5") (pinfunction "K_5") (pintype "bidirectional"))
      (node (ref "U$5") (pin "5") (pinfunction "K_5") (pintype "bidirectional"))
    )
    (net (code "195") (name "Net-(HT16K33-ROW14{slash}K12)") (class "Default")
      (node (ref "HT16K33") (pin "P$11") (pinfunction "ROW14/K12_P$11") (pintype "bidirectional"))
      (node (ref "U$2") (pin "8") (pinfunction "DP_8") (pintype "bidirectional"))
      (node (ref "U$3") (pin "8") (pinfunction "DP_8") (pintype "bidirectional"))
      (node (ref "U$4") (pin "8") (pinfunction "DP_8") (pintype "bidirectional"))
      (node (ref "U$5") (pin "8") (pinfunction "DP_8") (pintype "bidirectional"))
    )
    (net (code "196") (name "VDD") (class "Default")
      (node (ref "HT16K2") (pin "P$28") (pinfunction "VDD_P$28") (pintype "bidirectional"))
      (node (ref "HT16K3") (pin "P$28") (pinfunction "VDD_P$28") (pintype "bidirectional"))
      (node (ref "HT16K33") (pin "P$28") (pinfunction "VDD_P$28") (pintype "bidirectional"))
      (node (ref "HT16K4") (pin "P$28") (pinfunction "VDD_P$28") (pintype "bidirectional"))
      (node (ref "HT16K5") (pin "P$28") (pinfunction "VDD_P$28") (pintype "bidirectional"))
      (node (ref "HT16K6") (pin "P$28") (pinfunction "VDD_P$28") (pintype "bidirectional"))
      (node (ref "HT16K7") (pin "P$28") (pinfunction "VDD_P$28") (pintype "bidirectional"))
      (node (ref "HT16K8") (pin "P$28") (pinfunction "VDD_P$28") (pintype "bidirectional"))
      (node (ref "J1") (pin "1") (pinfunction "1_1") (pintype "passive"))
      (node (ref "J2") (pin "2") (pinfunction "2_2") (pintype "passive"))
      (node (ref "R11") (pin "1") (pinfunction "1_1") (pintype "passive"))
      (node (ref "R12") (pin "1") (pinfunction "1_1") (pintype "passive"))
      (node (ref "R16") (pin "1") (pinfunction "1_1") (pintype "passive"))
      (node (ref "R17") (pin "1") (pinfunction "1_1") (pintype "passive"))
      (node (ref "R18") (pin "1") (pinfunction "1_1") (pintype "passive"))
      (node (ref "R19") (pin "1") (pinfunction "1_1") (pintype "passive"))
      (node (ref "R26") (pin "1") (pinfunction "1_1") (pintype "passive"))
      (node (ref "R27") (pin "1") (pinfunction "1_1") (pintype "passive"))
      (node (ref "R31") (pin "1") (pinfunction "1_1") (pintype "passive"))
      (node (ref "R32") (pin "1") (pinfunction "1_1") (pintype "passive"))
      (node (ref "R36") (pin "1") (pinfunction "1_1") (pintype "passive"))
      (node (ref "R37") (pin "1") (pinfunction "1_1") (pintype "passive"))
      (node (ref "R41") (pin "1") (pinfunction "1_1") (pintype "passive"))
      (node (ref "R42") (pin "1") (pinfunction "1_1") (pintype "passive"))
      (node (ref "R6") (pin "1") (pinfunction "1_1") (pintype "passive"))
      (node (ref "R7") (pin "1") (pinfunction "1_1") (pintype "passive"))
    )
    (net (code "197") (name "unconnected-(HT16K2-ROW15{slash}K13{slash}INT-PadP$10)") (class "Default")
      (node (ref "HT16K2") (pin "P$10") (pinfunction "ROW15/K13/INT_P$10") (pintype "bidirectional"))
    )
    (net (code "198") (name "unconnected-(HT16K3-ROW15{slash}K13{slash}INT-PadP$10)") (class "Default")
      (node (ref "HT16K3") (pin "P$10") (pinfunction "ROW15/K13/INT_P$10") (pintype "bidirectional"))
    )
    (net (code "199") (name "unconnected-(HT16K4-ROW15{slash}K13{slash}INT-PadP$10)") (class "Default")
      (node (ref "HT16K4") (pin "P$10") (pinfunction "ROW15/K13/INT_P$10") (pintype "bidirectional"))
    )
    (net (code "200") (name "unconnected-(HT16K5-ROW15{slash}K13{slash}INT-PadP$10)") (class "Default")
      (node (ref "HT16K5") (pin "P$10") (pinfunction "ROW15/K13/INT_P$10") (pintype "bidirectional"))
    )
    (net (code "201") (name "unconnected-(HT16K6-ROW15{slash}K13{slash}INT-PadP$10)") (class "Default")
      (node (ref "HT16K6") (pin "P$10") (pinfunction "ROW15/K13/INT_P$10") (pintype "bidirectional"))
    )
    (net (code "202") (name "unconnected-(HT16K7-ROW15{slash}K13{slash}INT-PadP$10)") (class "Default")
      (node (ref "HT16K7") (pin "P$10") (pinfunction "ROW15/K13/INT_P$10") (pintype "bidirectional"))
    )
    (net (code "203") (name "unconnected-(HT16K8-ROW15{slash}K13{slash}INT-PadP$10)") (class "Default")
      (node (ref "HT16K8") (pin "P$10") (pinfunction "ROW15/K13/INT_P$10") (pintype "bidirectional"))
    )
    (net (code "204") (name "unconnected-(HT16K33-ROW15{slash}K13{slash}INT-PadP$10)") (class "Default")
      (node (ref "HT16K33") (pin "P$10") (pinfunction "ROW15/K13/INT_P$10") (pintype "bidirectional"))
    )
    (net (code "205") (name "unconnected-(R8-Pad2)") (class "Default")
      (node (ref "R8") (pin "2") (pinfunction "2_2") (pintype "passive"))
    )
    (net (code "206") (name "unconnected-(R10-Pad2)") (class "Default")
      (node (ref "R10") (pin "2") (pinfunction "2_2") (pintype "passive"))
    )
    (net (code "207") (name "unconnected-(R14-Pad2)") (class "Default")
      (node (ref "R14") (pin "2") (pinfunction "2_2") (pintype "passive"))
    )
    (net (code "208") (name "unconnected-(R15-Pad2)") (class "Default")
      (node (ref "R15") (pin "2") (pinfunction "2_2") (pintype "passive"))
    )
    (net (code "209") (name "unconnected-(R20-Pad2)") (class "Default")
      (node (ref "R20") (pin "2") (pinfunction "2_2") (pintype "passive"))
    )
    (net (code "210") (name "unconnected-(R21-Pad2)") (class "Default")
      (node (ref "R21") (pin "2") (pinfunction "2_2") (pintype "passive"))
    )
    (net (code "211") (name "unconnected-(R22-Pad2)") (class "Default")
      (node (ref "R22") (pin "2") (pinfunction "2_2") (pintype "passive"))
    )
    (net (code "212") (name "unconnected-(R25-Pad2)") (class "Default")
      (node (ref "R25") (pin "2") (pinfunction "2_2") (pintype "passive"))
    )
    (net (code "213") (name "unconnected-(R28-Pad2)") (class "Default")
      (node (ref "R28") (pin "2") (pinfunction "2_2") (pintype "passive"))
    )
    (net (code "214") (name "unconnected-(R29-Pad2)") (class "Default")
      (node (ref "R29") (pin "2") (pinfunction "2_2") (pintype "passive"))
    )
    (net (code "215") (name "unconnected-(R33-Pad2)") (class "Default")
      (node (ref "R33") (pin "2") (pinfunction "2_2") (pintype "passive"))
    )
    (net (code "216") (name "unconnected-(R39-Pad2)") (class "Default")
      (node (ref "R39") (pin "2") (pinfunction "2_2") (pintype "passive"))
    )
  )
)
